# BlueBus.net
KiCad netlist of a schematic drawn in EAGLE
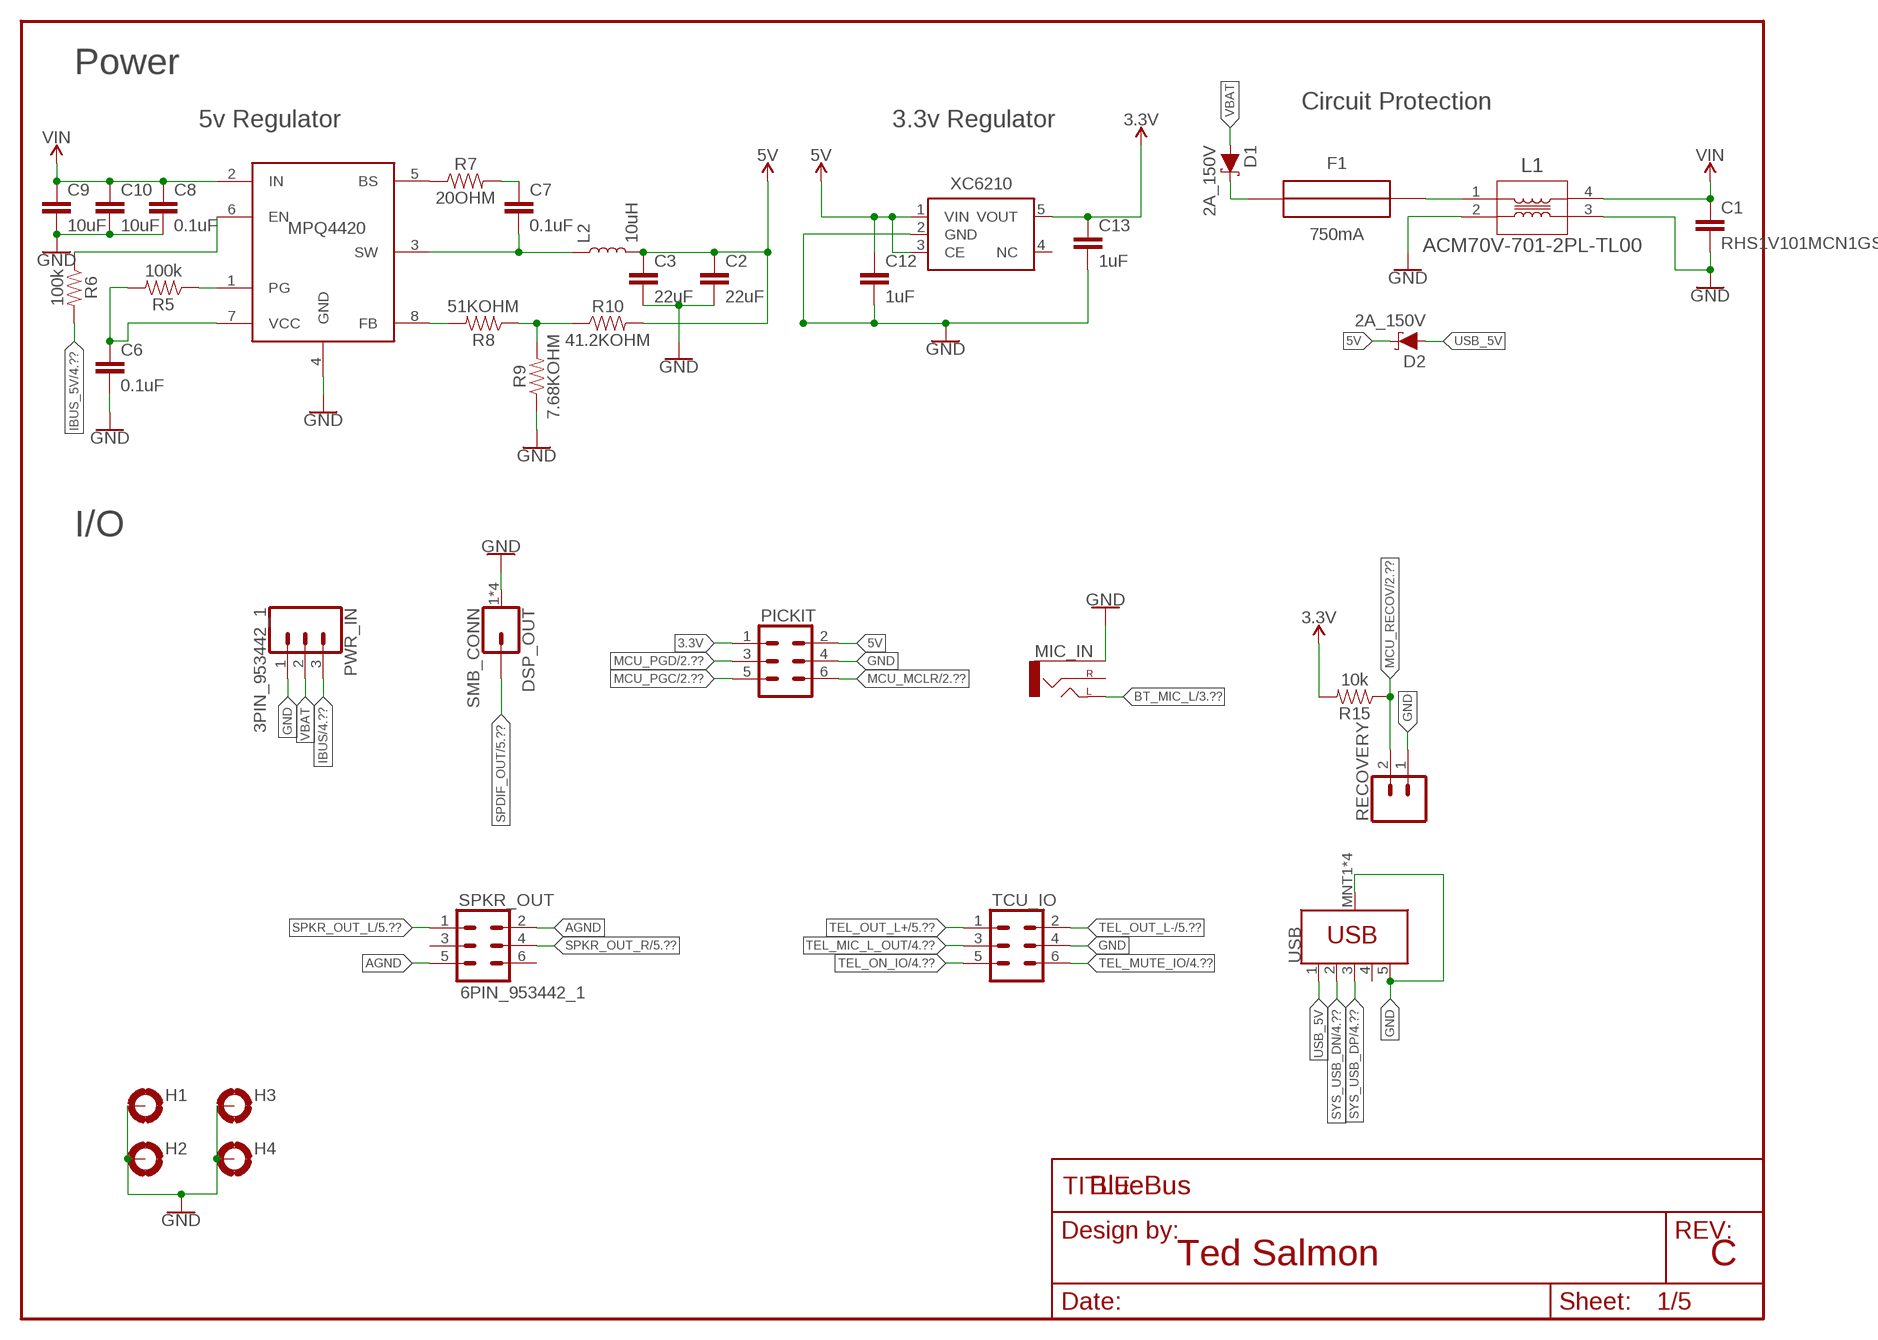
[diagram p0: schematic, sheet 1]
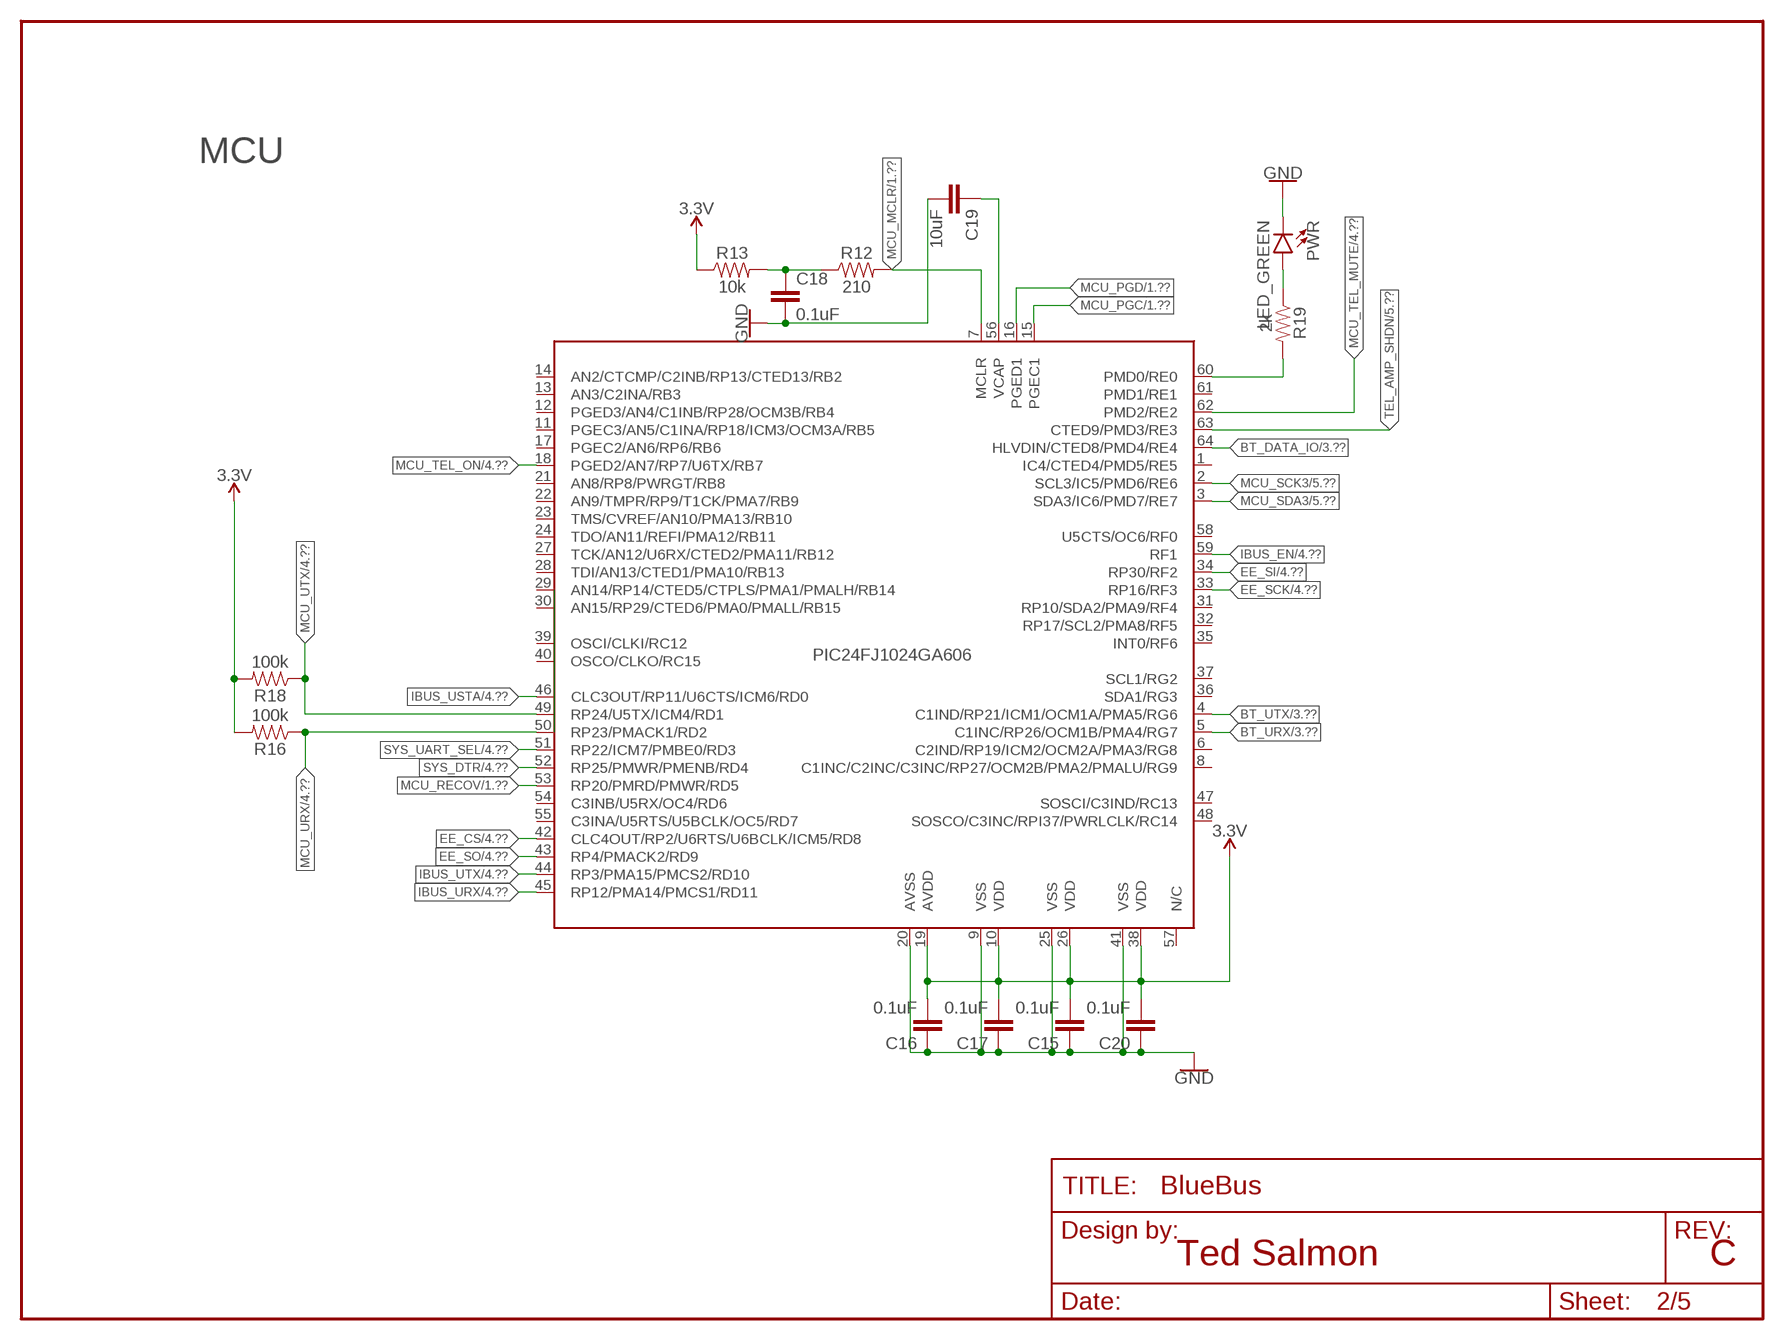
[diagram p1: schematic, sheet 2]
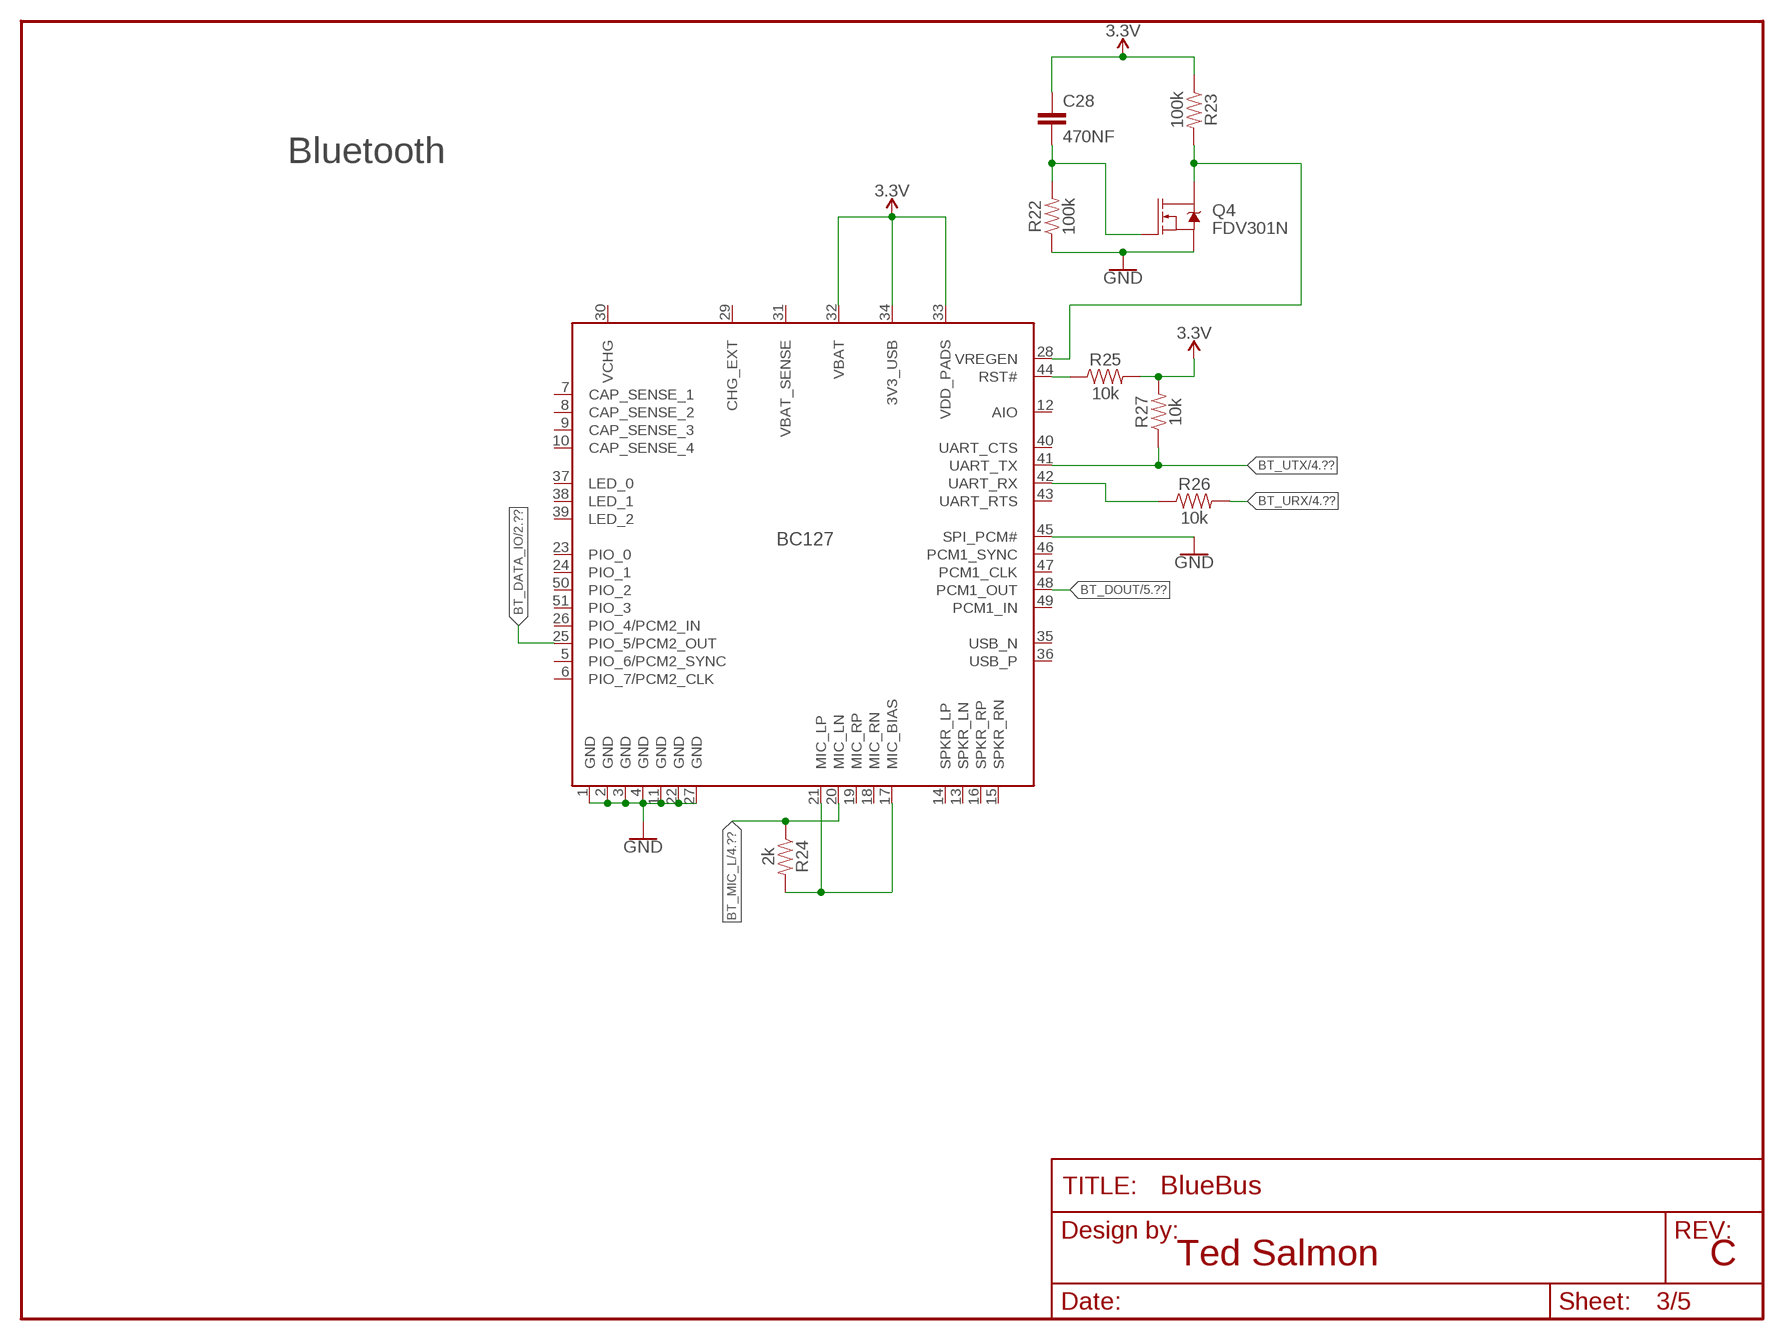
[diagram p2: schematic, sheet 3]
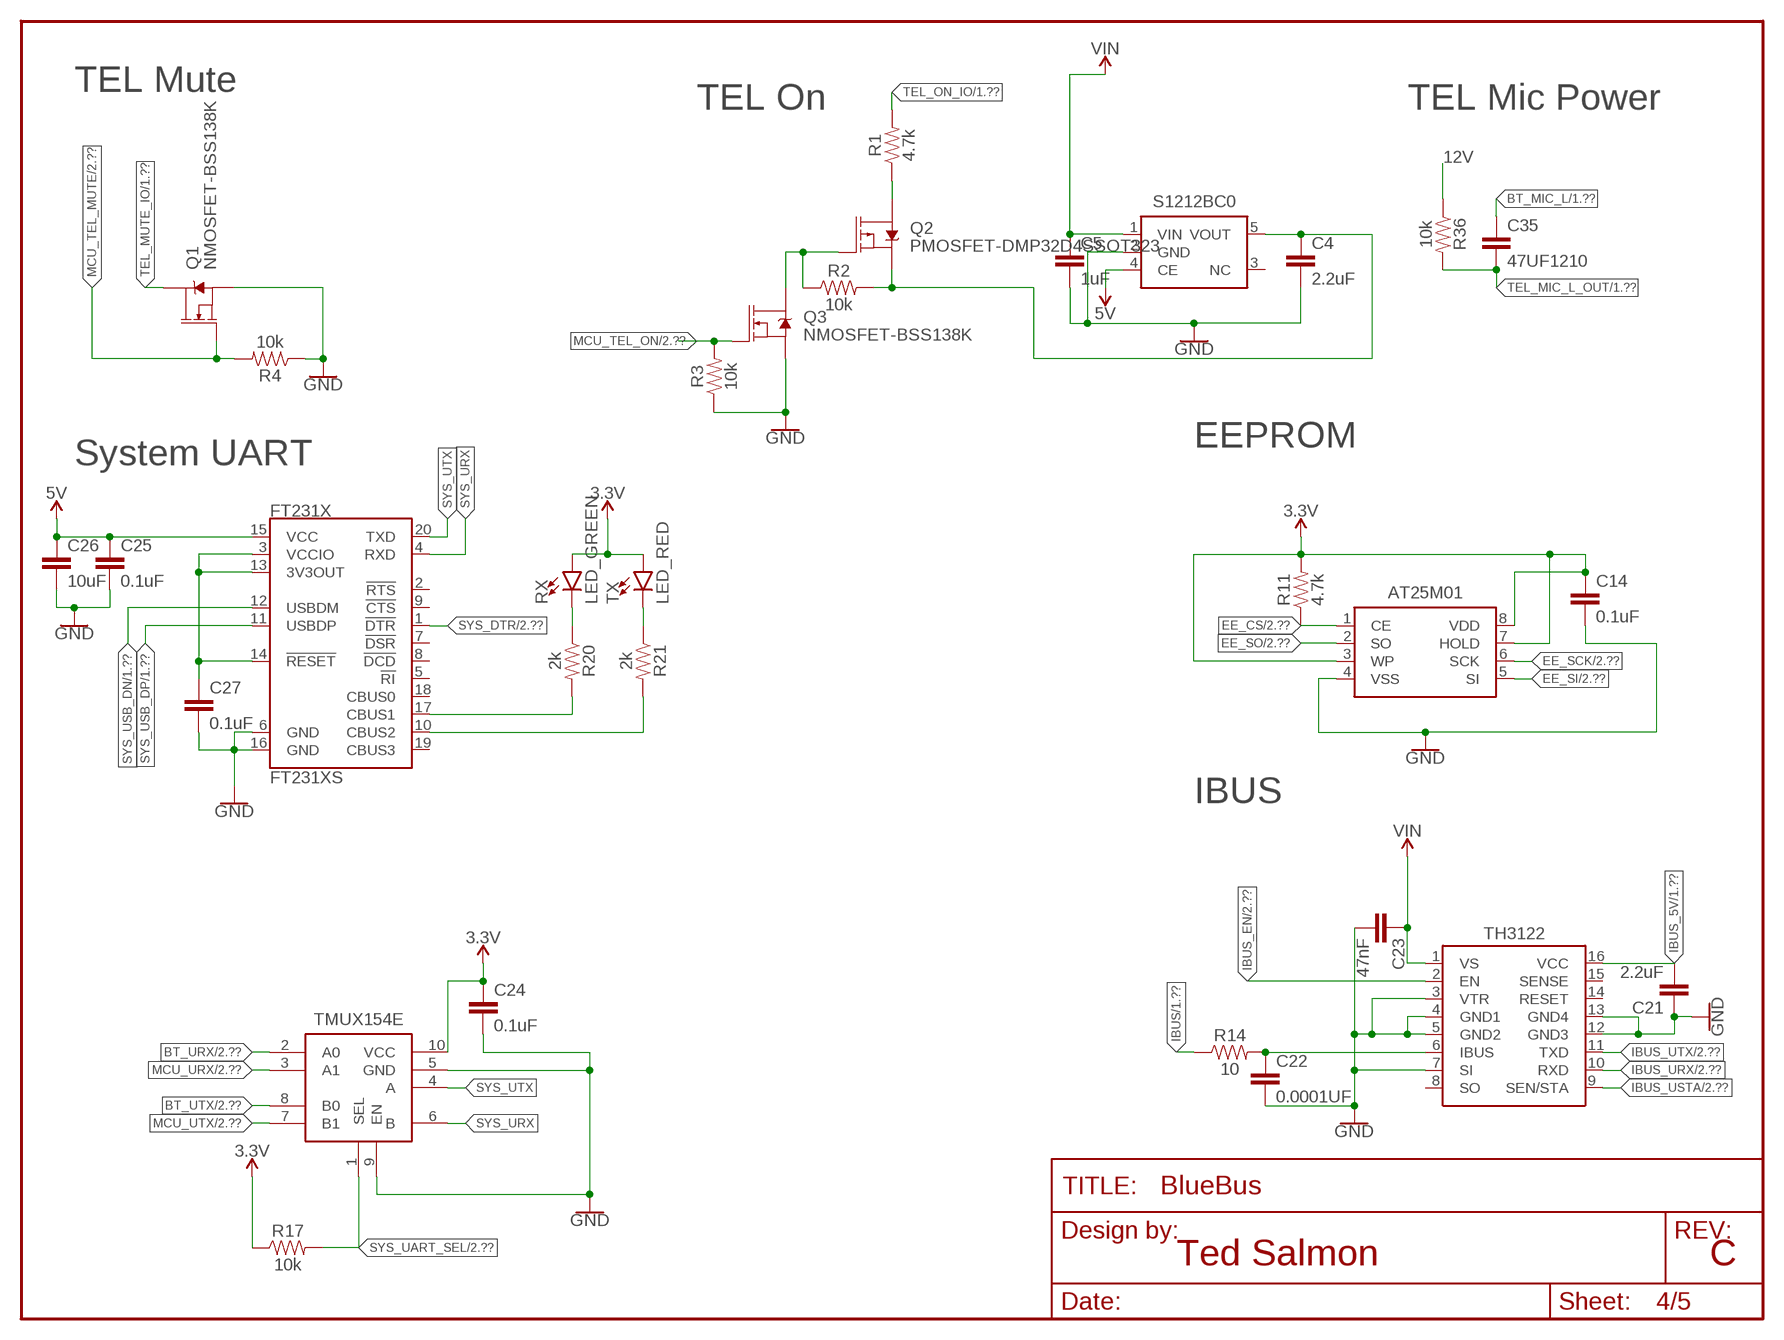
[diagram p3: schematic, sheet 4]
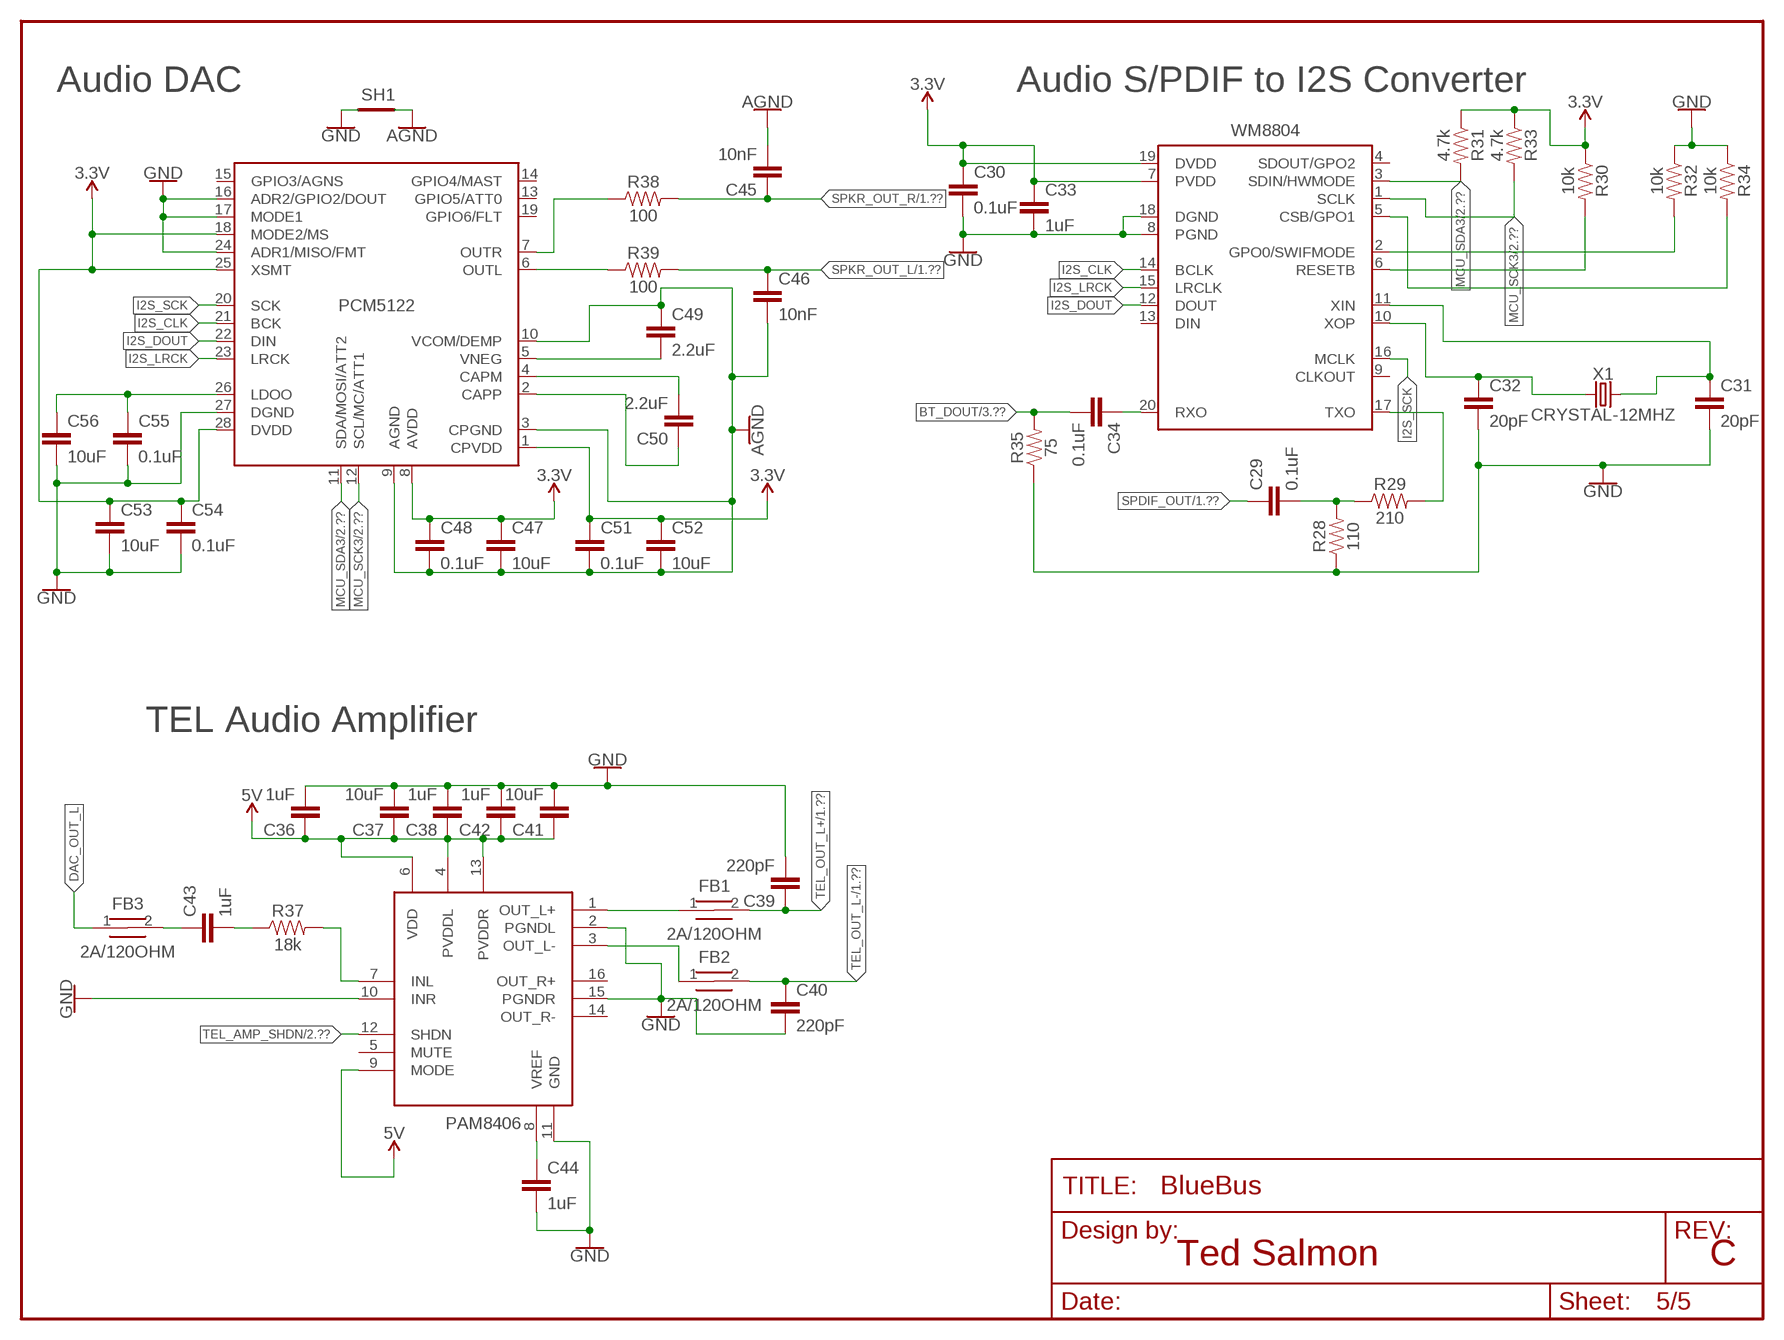
[diagram p4: schematic, sheet 5]

(export (version "E")
  (design (tool "Eeschema 10.0.6"))
  (components
    (comp (ref "C29")
      (value "0.1uF")
      (footprint "eagle-import:0805")
      (fields (field (name "MFG") "KEMET"))
      (libsource (lib "eagle-import") (part "0.1UF"))
    )
    (comp (ref "C30")
      (value "0.1uF")
      (footprint "eagle-import:0805")
      (fields (field (name "MFG") "KEMET"))
      (libsource (lib "eagle-import") (part "0.1UF"))
    )
    (comp (ref "C31")
      (value "20pF")
      (footprint "eagle-import:0805")
      (libsource (lib "eagle-import") (part "20PF"))
    )
    (comp (ref "C32")
      (value "20pF")
      (footprint "eagle-import:0805")
      (libsource (lib "eagle-import") (part "20PF"))
    )
    (comp (ref "C33")
      (value "1uF")
      (footprint "eagle-import:0805")
      (fields (field (name "MFG") "TDK"))
      (libsource (lib "eagle-import") (part "1UF"))
    )
    (comp (ref "C34")
      (value "0.1uF")
      (footprint "eagle-import:0805")
      (fields (field (name "MFG") "KEMET"))
      (libsource (lib "eagle-import") (part "0.1UF"))
    )
    (comp (ref "C36")
      (value "1uF")
      (footprint "eagle-import:0805")
      (fields (field (name "MFG") "TDK"))
      (libsource (lib "eagle-import") (part "1UF"))
    )
    (comp (ref "C37")
      (value "10uF")
      (footprint "eagle-import:0805")
      (fields (field (name "MFG") "TDK"))
      (libsource (lib "eagle-import") (part "10UF2012"))
    )
    (comp (ref "C38")
      (value "1uF")
      (footprint "eagle-import:0805")
      (fields (field (name "MFG") "TDK"))
      (libsource (lib "eagle-import") (part "1UF"))
    )
    (comp (ref "C39")
      (value "220pF")
      (footprint "eagle-import:0805")
      (fields (field (name "MFG") "KEMET"))
      (libsource (lib "eagle-import") (part "220PF"))
    )
    (comp (ref "C40")
      (value "220pF")
      (footprint "eagle-import:0805")
      (fields (field (name "MFG") "KEMET"))
      (libsource (lib "eagle-import") (part "220PF"))
    )
    (comp (ref "C41")
      (value "10uF")
      (footprint "eagle-import:0805")
      (fields (field (name "MFG") "TDK"))
      (libsource (lib "eagle-import") (part "10UF2012"))
    )
    (comp (ref "C42")
      (value "1uF")
      (footprint "eagle-import:0805")
      (fields (field (name "MFG") "TDK"))
      (libsource (lib "eagle-import") (part "1UF"))
    )
    (comp (ref "C43")
      (value "1uF")
      (footprint "eagle-import:0805")
      (fields (field (name "MFG") "TDK"))
      (libsource (lib "eagle-import") (part "1UF"))
    )
    (comp (ref "C44")
      (value "1uF")
      (footprint "eagle-import:0805")
      (fields (field (name "MFG") "TDK"))
      (libsource (lib "eagle-import") (part "1UF"))
    )
    (comp (ref "C45")
      (value "10nF")
      (footprint "eagle-import:0805")
      (fields (field (name "MFG") "KEMET"))
      (libsource (lib "eagle-import") (part "10NF"))
    )
    (comp (ref "C46")
      (value "10nF")
      (footprint "eagle-import:0805")
      (fields (field (name "MFG") "KEMET"))
      (libsource (lib "eagle-import") (part "10NF"))
    )
    (comp (ref "C47")
      (value "10uF")
      (footprint "eagle-import:0805")
      (fields (field (name "MFG") "TDK"))
      (libsource (lib "eagle-import") (part "10UF2012"))
    )
    (comp (ref "C48")
      (value "0.1uF")
      (footprint "eagle-import:0805")
      (fields (field (name "MFG") "KEMET"))
      (libsource (lib "eagle-import") (part "0.1UF"))
    )
    (comp (ref "C49")
      (value "2.2uF")
      (footprint "eagle-import:0805")
      (fields (field (name "MFG") "TDK"))
      (libsource (lib "eagle-import") (part "2.2UF"))
    )
    (comp (ref "C50")
      (value "2.2uF")
      (footprint "eagle-import:0805")
      (fields (field (name "MFG") "TDK"))
      (libsource (lib "eagle-import") (part "2.2UF"))
    )
    (comp (ref "C51")
      (value "0.1uF")
      (footprint "eagle-import:0805")
      (fields (field (name "MFG") "KEMET"))
      (libsource (lib "eagle-import") (part "0.1UF"))
    )
    (comp (ref "C52")
      (value "10uF")
      (footprint "eagle-import:0805")
      (fields (field (name "MFG") "TDK"))
      (libsource (lib "eagle-import") (part "10UF2012"))
    )
    (comp (ref "C53")
      (value "10uF")
      (footprint "eagle-import:0805")
      (fields (field (name "MFG") "TDK"))
      (libsource (lib "eagle-import") (part "10UF2012"))
    )
    (comp (ref "C54")
      (value "0.1uF")
      (footprint "eagle-import:0805")
      (fields (field (name "MFG") "KEMET"))
      (libsource (lib "eagle-import") (part "0.1UF"))
    )
    (comp (ref "C55")
      (value "0.1uF")
      (footprint "eagle-import:0805")
      (fields (field (name "MFG") "KEMET"))
      (libsource (lib "eagle-import") (part "0.1UF"))
    )
    (comp (ref "C56")
      (value "10uF")
      (footprint "eagle-import:0805")
      (fields (field (name "MFG") "TDK"))
      (libsource (lib "eagle-import") (part "10UF2012"))
    )
    (comp (ref "FB1")
      (value "2A/120OHM")
      (footprint "eagle-import:0805")
      (fields (field (name "MFG") "BOURNS"))
      (libsource (lib "eagle-import") (part "FERRITE_2A/120OHM"))
    )
    (comp (ref "FB2")
      (value "2A/120OHM")
      (footprint "eagle-import:0805")
      (fields (field (name "MFG") "BOURNS"))
      (libsource (lib "eagle-import") (part "FERRITE_2A/120OHM"))
    )
    (comp (ref "FB3")
      (value "2A/120OHM")
      (footprint "eagle-import:0805")
      (fields (field (name "MFG") "BOURNS"))
      (libsource (lib "eagle-import") (part "FERRITE_2A/120OHM"))
    )
    (comp (ref "FRAME5")
      (value "FRAME-LETTER")
      (footprint "eagle-import:DUMMY")
      (libsource (lib "eagle-import") (part "FRAME-LETTER"))
    )
    (comp (ref "PAM8406")
      (value "PAM8406")
      (footprint "eagle-import:SOP-16")
      (libsource (lib "eagle-import") (part "PAM8406"))
    )
    (comp (ref "PCM5122")
      (value "PCM5122")
      (footprint "eagle-import:TSSOP28")
      (libsource (lib "eagle-import") (part "PCM5122"))
    )
    (comp (ref "R28")
      (value "110")
      (footprint "eagle-import:0805")
      (libsource (lib "eagle-import") (part "110OHM"))
    )
    (comp (ref "R29")
      (value "210")
      (footprint "eagle-import:0805")
      (libsource (lib "eagle-import") (part "210OHM"))
    )
    (comp (ref "R30")
      (value "10k")
      (footprint "eagle-import:0805")
      (fields (field (name "MFG") "Panasonic"))
      (libsource (lib "eagle-import") (part "10KOHM"))
    )
    (comp (ref "R31")
      (value "4.7k")
      (footprint "eagle-import:0805")
      (fields (field (name "MFG") "Panasonic"))
      (libsource (lib "eagle-import") (part "4.7KOHM"))
    )
    (comp (ref "R32")
      (value "10k")
      (footprint "eagle-import:0805")
      (fields (field (name "MFG") "Panasonic"))
      (libsource (lib "eagle-import") (part "10KOHM"))
    )
    (comp (ref "R33")
      (value "4.7k")
      (footprint "eagle-import:0805")
      (fields (field (name "MFG") "Panasonic"))
      (libsource (lib "eagle-import") (part "4.7KOHM"))
    )
    (comp (ref "R34")
      (value "10k")
      (footprint "eagle-import:0805")
      (fields (field (name "MFG") "Panasonic"))
      (libsource (lib "eagle-import") (part "10KOHM"))
    )
    (comp (ref "R35")
      (value "75")
      (footprint "eagle-import:0805")
      (fields (field (name "MFG") "Panasonic"))
      (libsource (lib "eagle-import") (part "75OHM"))
    )
    (comp (ref "R37")
      (value "18k")
      (footprint "eagle-import:0805")
      (fields (field (name "MFG") "Panasonic"))
      (libsource (lib "eagle-import") (part "18KOHM"))
    )
    (comp (ref "R38")
      (value "100")
      (footprint "eagle-import:0805")
      (fields (field (name "MFG") "PANASONIC"))
      (libsource (lib "eagle-import") (part "100OHM"))
    )
    (comp (ref "R39")
      (value "100")
      (footprint "eagle-import:0805")
      (fields (field (name "MFG") "PANASONIC"))
      (libsource (lib "eagle-import") (part "100OHM"))
    )
    (comp (ref "SH1")
      (value "SHORTT5")
      (footprint "eagle-import:SHORT_TOP-50")
      (libsource (lib "eagle-import") (part "SHORTT5"))
    )
    (comp (ref "WM8804")
      (value "WM8804")
      (footprint "eagle-import:SSOP20")
      (libsource (lib "eagle-import") (part "WM8804"))
    )
    (comp (ref "X1")
      (value "CRYSTAL-12MHZ")
      (footprint "eagle-import:HC49")
      (libsource (lib "eagle-import") (part "CRYSTAL-12MHZ"))
    )
    (comp (ref "BC127")
      (value "BC127")
      (footprint "eagle-import:BC127")
      (libsource (lib "eagle-import") (part "BC127"))
    )
    (comp (ref "C28")
      (value "470NF")
      (footprint "eagle-import:0805")
      (fields (field (name "MFG") "TDK"))
      (libsource (lib "eagle-import") (part "470NF"))
    )
    (comp (ref "FRAME4")
      (value "FRAME-LETTER")
      (footprint "eagle-import:DUMMY")
      (libsource (lib "eagle-import") (part "FRAME-LETTER"))
    )
    (comp (ref "Q4")
      (value "FDV301N")
      (footprint "eagle-import:SOT-23")
      (libsource (lib "eagle-import") (part "FDV301N"))
    )
    (comp (ref "R22")
      (value "100k")
      (footprint "eagle-import:0805")
      (libsource (lib "eagle-import") (part "100KOHM"))
    )
    (comp (ref "R23")
      (value "100k")
      (footprint "eagle-import:0805")
      (libsource (lib "eagle-import") (part "100KOHM"))
    )
    (comp (ref "R24")
      (value "2k")
      (footprint "eagle-import:0805")
      (fields (field (name "MFG") "ROHM"))
      (libsource (lib "eagle-import") (part "2KOHM"))
    )
    (comp (ref "R25")
      (value "10k")
      (footprint "eagle-import:0805")
      (fields (field (name "MFG") "Panasonic"))
      (libsource (lib "eagle-import") (part "10KOHM"))
    )
    (comp (ref "R26")
      (value "10k")
      (footprint "eagle-import:0805")
      (fields (field (name "MFG") "Panasonic"))
      (libsource (lib "eagle-import") (part "10KOHM"))
    )
    (comp (ref "R27")
      (value "10k")
      (footprint "eagle-import:0805")
      (fields (field (name "MFG") "Panasonic"))
      (libsource (lib "eagle-import") (part "10KOHM"))
    )
    (comp (ref "C15")
      (value "0.1uF")
      (footprint "eagle-import:0805")
      (fields (field (name "MFG") "KEMET"))
      (libsource (lib "eagle-import") (part "0.1UF"))
    )
    (comp (ref "C16")
      (value "0.1uF")
      (footprint "eagle-import:0805")
      (fields (field (name "MFG") "KEMET"))
      (libsource (lib "eagle-import") (part "0.1UF"))
    )
    (comp (ref "C17")
      (value "0.1uF")
      (footprint "eagle-import:0805")
      (fields (field (name "MFG") "KEMET"))
      (libsource (lib "eagle-import") (part "0.1UF"))
    )
    (comp (ref "C18")
      (value "0.1uF")
      (footprint "eagle-import:0805")
      (fields (field (name "MFG") "KEMET"))
      (libsource (lib "eagle-import") (part "0.1UF"))
    )
    (comp (ref "C19")
      (value "10uF")
      (footprint "eagle-import:0805")
      (fields (field (name "MFG") "TDK"))
      (libsource (lib "eagle-import") (part "10UF2012"))
    )
    (comp (ref "C20")
      (value "0.1uF")
      (footprint "eagle-import:0805")
      (fields (field (name "MFG") "KEMET"))
      (libsource (lib "eagle-import") (part "0.1UF"))
    )
    (comp (ref "FRAME2")
      (value "FRAME-LETTER")
      (footprint "eagle-import:DUMMY")
      (libsource (lib "eagle-import") (part "FRAME-LETTER"))
    )
    (comp (ref "PIC24FJ1024GA606")
      (value "PIC24FJ1024GA606")
      (footprint "eagle-import:TQFP64")
      (libsource (lib "eagle-import") (part "PIC24FJ1024GA606"))
    )
    (comp (ref "PWR")
      (value "LED_GREEN")
      (footprint "eagle-import:LED-0805")
      (libsource (lib "eagle-import") (part "LED_GREEN"))
    )
    (comp (ref "R12")
      (value "210")
      (footprint "eagle-import:0805")
      (libsource (lib "eagle-import") (part "210OHM"))
    )
    (comp (ref "R13")
      (value "10k")
      (footprint "eagle-import:0805")
      (fields (field (name "MFG") "Panasonic"))
      (libsource (lib "eagle-import") (part "10KOHM"))
    )
    (comp (ref "R16")
      (value "100k")
      (footprint "eagle-import:0805")
      (libsource (lib "eagle-import") (part "100KOHM"))
    )
    (comp (ref "R18")
      (value "100k")
      (footprint "eagle-import:0805")
      (libsource (lib "eagle-import") (part "100KOHM"))
    )
    (comp (ref "R19")
      (value "2k")
      (footprint "eagle-import:0805")
      (fields (field (name "MFG") "ROHM"))
      (libsource (lib "eagle-import") (part "2KOHM"))
    )
    (comp (ref "AT25M01")
      (value "AT25M01-SHM")
      (footprint "eagle-import:SOIJ-8")
      (libsource (lib "eagle-import") (part "AT25M01-SHM"))
    )
    (comp (ref "C4")
      (value "2.2uF")
      (footprint "eagle-import:0805")
      (fields (field (name "MFG") "TDK"))
      (libsource (lib "eagle-import") (part "2.2UF"))
    )
    (comp (ref "C5")
      (value "1uF")
      (footprint "eagle-import:0805")
      (fields (field (name "MFG") "TDK"))
      (libsource (lib "eagle-import") (part "1UF"))
    )
    (comp (ref "C14")
      (value "0.1uF")
      (footprint "eagle-import:0805")
      (fields (field (name "MFG") "KEMET"))
      (libsource (lib "eagle-import") (part "0.1UF"))
    )
    (comp (ref "C21")
      (value "2.2uF")
      (footprint "eagle-import:0805")
      (fields (field (name "MFG") "TDK"))
      (libsource (lib "eagle-import") (part "2.2UF"))
    )
    (comp (ref "C22")
      (value "0.0001UF")
      (footprint "eagle-import:0805")
      (libsource (lib "eagle-import") (part "0.0001UF"))
    )
    (comp (ref "C23")
      (value "47nF")
      (footprint "eagle-import:0805")
      (fields (field (name "MFG") "AVX"))
      (libsource (lib "eagle-import") (part "47NF"))
    )
    (comp (ref "C24")
      (value "0.1uF")
      (footprint "eagle-import:0805")
      (fields (field (name "MFG") "KEMET"))
      (libsource (lib "eagle-import") (part "0.1UF"))
    )
    (comp (ref "C25")
      (value "0.1uF")
      (footprint "eagle-import:0805")
      (fields (field (name "MFG") "KEMET"))
      (libsource (lib "eagle-import") (part "0.1UF"))
    )
    (comp (ref "C26")
      (value "10uF")
      (footprint "eagle-import:0805")
      (fields (field (name "MFG") "TDK"))
      (libsource (lib "eagle-import") (part "10UF2012"))
    )
    (comp (ref "C27")
      (value "0.1uF")
      (footprint "eagle-import:0805")
      (fields (field (name "MFG") "KEMET"))
      (libsource (lib "eagle-import") (part "0.1UF"))
    )
    (comp (ref "C35")
      (value "47UF1210")
      (footprint "eagle-import:1210")
      (libsource (lib "eagle-import") (part "47UF1210"))
    )
    (comp (ref "FRAME3")
      (value "FRAME-LETTER")
      (footprint "eagle-import:DUMMY")
      (libsource (lib "eagle-import") (part "FRAME-LETTER"))
    )
    (comp (ref "FT231X")
      (value "FT231XS")
      (footprint "eagle-import:SSOP20_L")
      (libsource (lib "eagle-import") (part "FT231XS"))
    )
    (comp (ref "Q1")
      (value "NMOSFET-BSS138K")
      (footprint "eagle-import:SOT-23")
      (libsource (lib "eagle-import") (part "NMOSFET-BSS138K"))
    )
    (comp (ref "Q2")
      (value "PMOSFET-DMP32D4SSOT323")
      (footprint "eagle-import:SOT323")
      (libsource (lib "eagle-import") (part "PMOSFET-DMP32D4SSOT323"))
    )
    (comp (ref "Q3")
      (value "NMOSFET-BSS138K")
      (footprint "eagle-import:SOT-23")
      (libsource (lib "eagle-import") (part "NMOSFET-BSS138K"))
    )
    (comp (ref "R1")
      (value "4.7k")
      (footprint "eagle-import:0805")
      (fields (field (name "MFG") "Panasonic"))
      (libsource (lib "eagle-import") (part "4.7KOHM"))
    )
    (comp (ref "R2")
      (value "10k")
      (footprint "eagle-import:0805")
      (fields (field (name "MFG") "Panasonic"))
      (libsource (lib "eagle-import") (part "10KOHM"))
    )
    (comp (ref "R3")
      (value "10k")
      (footprint "eagle-import:0805")
      (fields (field (name "MFG") "Panasonic"))
      (libsource (lib "eagle-import") (part "10KOHM"))
    )
    (comp (ref "R4")
      (value "10k")
      (footprint "eagle-import:0805")
      (fields (field (name "MFG") "Panasonic"))
      (libsource (lib "eagle-import") (part "10KOHM"))
    )
    (comp (ref "R11")
      (value "4.7k")
      (footprint "eagle-import:0805")
      (fields (field (name "MFG") "Panasonic"))
      (libsource (lib "eagle-import") (part "4.7KOHM"))
    )
    (comp (ref "R14")
      (value "10")
      (footprint "eagle-import:0805")
      (fields (field (name "MFG") "Panasonic"))
      (libsource (lib "eagle-import") (part "10OHM"))
    )
    (comp (ref "R17")
      (value "10k")
      (footprint "eagle-import:0805")
      (fields (field (name "MFG") "Panasonic"))
      (libsource (lib "eagle-import") (part "10KOHM"))
    )
    (comp (ref "R20")
      (value "2k")
      (footprint "eagle-import:0805")
      (fields (field (name "MFG") "ROHM"))
      (libsource (lib "eagle-import") (part "2KOHM"))
    )
    (comp (ref "R21")
      (value "2k")
      (footprint "eagle-import:0805")
      (fields (field (name "MFG") "ROHM"))
      (libsource (lib "eagle-import") (part "2KOHM"))
    )
    (comp (ref "R36")
      (value "10k")
      (footprint "eagle-import:0805")
      (fields (field (name "MFG") "Panasonic"))
      (libsource (lib "eagle-import") (part "10KOHM"))
    )
    (comp (ref "RX")
      (value "LED_GREEN")
      (footprint "eagle-import:LED-0805")
      (libsource (lib "eagle-import") (part "LED_GREEN"))
    )
    (comp (ref "S1212BC0")
      (value "S-1212BC0-M5T1U")
      (footprint "eagle-import:SOT23-5")
      (libsource (lib "eagle-import") (part "S-1212BC0-M5T1U"))
    )
    (comp (ref "TH3122")
      (value "TH3122.4")
      (footprint "eagle-import:SOIC16DF")
      (libsource (lib "eagle-import") (part "TH3122.4"))
    )
    (comp (ref "TMUX154E")
      (value "TMUX154E")
      (footprint "eagle-import:VSSOP10")
      (libsource (lib "eagle-import") (part "TMUX154E"))
    )
    (comp (ref "TX")
      (value "LED_RED")
      (footprint "eagle-import:LED-0805")
      (libsource (lib "eagle-import") (part "LED_RED"))
    )
    (comp (ref "C1")
      (value "RHS1V101MCN1GS")
      (footprint "eagle-import:RHS1V101MCN1GS")
      (fields (field (name "MFG") "Nichicon"))
      (libsource (lib "eagle-import") (part "RHS1V101MCN1GS"))
    )
    (comp (ref "C2")
      (value "22uF")
      (footprint "eagle-import:0805")
      (fields (field (name "MFG") "TDK"))
      (libsource (lib "eagle-import") (part "22UF"))
    )
    (comp (ref "C3")
      (value "22uF")
      (footprint "eagle-import:0805")
      (fields (field (name "MFG") "TDK"))
      (libsource (lib "eagle-import") (part "22UF"))
    )
    (comp (ref "C6")
      (value "0.1uF")
      (footprint "eagle-import:0805")
      (fields (field (name "MFG") "KEMET"))
      (libsource (lib "eagle-import") (part "0.1UF"))
    )
    (comp (ref "C7")
      (value "0.1uF")
      (footprint "eagle-import:0805")
      (fields (field (name "MFG") "KEMET"))
      (libsource (lib "eagle-import") (part "0.1UF"))
    )
    (comp (ref "C8")
      (value "0.1uF")
      (footprint "eagle-import:0805")
      (fields (field (name "MFG") "KEMET"))
      (libsource (lib "eagle-import") (part "0.1UF"))
    )
    (comp (ref "C9")
      (value "10uF")
      (footprint "eagle-import:1206")
      (fields (field (name "MFG") "TDK"))
      (libsource (lib "eagle-import") (part "10UF"))
    )
    (comp (ref "C10")
      (value "10uF")
      (footprint "eagle-import:1206")
      (fields (field (name "MFG") "TDK"))
      (libsource (lib "eagle-import") (part "10UF"))
    )
    (comp (ref "C12")
      (value "1uF")
      (footprint "eagle-import:0805")
      (fields (field (name "MFG") "TDK"))
      (libsource (lib "eagle-import") (part "1UF"))
    )
    (comp (ref "C13")
      (value "1uF")
      (footprint "eagle-import:0805")
      (fields (field (name "MFG") "TDK"))
      (libsource (lib "eagle-import") (part "1UF"))
    )
    (comp (ref "D1")
      (value "2A_150V")
      (footprint "eagle-import:SOD123FL-2")
      (fields (field (name "MFG") "MCC"))
      (libsource (lib "eagle-import") (part "SMD2150PL_2A_150V"))
    )
    (comp (ref "D2")
      (value "2A_150V")
      (footprint "eagle-import:SOD123FL-2")
      (fields (field (name "MFG") "MCC"))
      (libsource (lib "eagle-import") (part "SMD2150PL_2A_150V"))
    )
    (comp (ref "DSP_OUT")
      (value "SMB_CONN")
      (footprint "eagle-import:MOLEX_SMB")
      (libsource (lib "eagle-import") (part "SMB_CONN"))
    )
    (comp (ref "F1")
      (value "750mA")
      (footprint "eagle-import:LITTLEFUSE")
      (fields (field (name "MFG") "LITTLEBLOCK"))
      (libsource (lib "eagle-import") (part "LITTLEBLOCK_FUSE_.75A"))
    )
    (comp (ref "FRAME1")
      (value "FRAME-LETTER")
      (footprint "eagle-import:DUMMY")
      (libsource (lib "eagle-import") (part "FRAME-LETTER"))
    )
    (comp (ref "H1")
      (value "2,2-PAD")
      (footprint "eagle-import:2.2-PAD")
      (libsource (lib "eagle-import") (part "2,2-PAD"))
    )
    (comp (ref "H2")
      (value "2,2-PAD")
      (footprint "eagle-import:2.2-PAD")
      (libsource (lib "eagle-import") (part "2,2-PAD"))
    )
    (comp (ref "H3")
      (value "2,2-PAD")
      (footprint "eagle-import:2.2-PAD")
      (libsource (lib "eagle-import") (part "2,2-PAD"))
    )
    (comp (ref "H4")
      (value "2,2-PAD")
      (footprint "eagle-import:2.2-PAD")
      (libsource (lib "eagle-import") (part "2,2-PAD"))
    )
    (comp (ref "L1")
      (value "ACM70V-701-2PL-TL00")
      (footprint "eagle-import:ACM70V-701-2PL-TL00")
      (fields (field (name "MFG") "TDK"))
      (libsource (lib "eagle-import") (part "ACM70V-701-2PL-TL00"))
    )
    (comp (ref "L2")
      (value "10uH")
      (footprint "eagle-import:MPL-SE5040")
      (fields (field (name "MFG") "MPS"))
      (libsource (lib "eagle-import") (part "MPL-SE5040-100"))
    )
    (comp (ref "MIC_IN")
      (value "AUDIO-CUI-SJ-3523-SMT")
      (footprint "eagle-import:AUDIO-CUI-SJ-352X-SMT")
      (libsource (lib "eagle-import") (part "AUDIO-CUI-SJ-3523-SMT"))
    )
    (comp (ref "MPQ4420")
      (value "MPQ4420")
      (footprint "eagle-import:TSOT23-8")
      (libsource (lib "eagle-import") (part "MPQ4420"))
    )
    (comp (ref "PICKIT")
      (value "6PIN_JUMPER")
      (footprint "eagle-import:2X3")
      (libsource (lib "eagle-import") (part "6PIN_JUMPER"))
    )
    (comp (ref "PWR_IN")
      (value "3PIN_953442_1")
      (footprint "eagle-import:TE_MQS_3PIN")
      (libsource (lib "eagle-import") (part "3PIN_953442_1"))
    )
    (comp (ref "R5")
      (value "100k")
      (footprint "eagle-import:0805")
      (libsource (lib "eagle-import") (part "100KOHM"))
    )
    (comp (ref "R6")
      (value "100k")
      (footprint "eagle-import:0805")
      (libsource (lib "eagle-import") (part "100KOHM"))
    )
    (comp (ref "R7")
      (value "20OHM")
      (footprint "eagle-import:0805")
      (libsource (lib "eagle-import") (part "20OHM"))
    )
    (comp (ref "R8")
      (value "51KOHM")
      (footprint "eagle-import:0805")
      (libsource (lib "eagle-import") (part "51KOHM"))
    )
    (comp (ref "R9")
      (value "7.68KOHM")
      (footprint "eagle-import:0805")
      (libsource (lib "eagle-import") (part "7.68KOHM"))
    )
    (comp (ref "R10")
      (value "41.2KOHM")
      (footprint "eagle-import:0805")
      (libsource (lib "eagle-import") (part "41.2KOHM"))
    )
    (comp (ref "R15")
      (value "10k")
      (footprint "eagle-import:0805")
      (fields (field (name "MFG") "Panasonic"))
      (libsource (lib "eagle-import") (part "10KOHM"))
    )
    (comp (ref "RECOVERY")
      (value "2PIN_JUMPER")
      (footprint "eagle-import:1X02")
      (libsource (lib "eagle-import") (part "2PIN_JUMPER"))
    )
    (comp (ref "SPKR_OUT")
      (value "6PIN_953442_1")
      (footprint "eagle-import:TE_MQS_6PIN")
      (libsource (lib "eagle-import") (part "6PIN_953442_1"))
    )
    (comp (ref "TCU_IO")
      (value "6PIN_5_103166_1")
      (footprint "eagle-import:TE_AMPMODU_6_PIN")
      (libsource (lib "eagle-import") (part "6PIN_5_103166_1"))
    )
    (comp (ref "USB")
      (value "USB3080-30-01-A")
      (footprint "eagle-import:USB3080-30-01-A")
      (fields (field (name "MFG") "GCT"))
      (libsource (lib "eagle-import") (part "USB3080-30-01-A"))
    )
    (comp (ref "XC6210")
      (value "XC6210SOT25")
      (footprint "eagle-import:SOT23-5")
      (libsource (lib "eagle-import") (part "XC6210SOT25"))
    )
  )
  (nets
    (net (code "1") (name "3.3V") (class "Default")
      (node (ref "AT25M01") (pin "3") (pinfunction "WP_3") (pintype "bidirectional"))
      (node (ref "AT25M01") (pin "7") (pinfunction "HOLD_7") (pintype "bidirectional"))
      (node (ref "AT25M01") (pin "8") (pinfunction "VDD_8") (pintype "power_in"))
      (node (ref "BC127") (pin "32") (pinfunction "VBAT_32") (pintype "bidirectional"))
      (node (ref "BC127") (pin "33") (pinfunction "VDD_PADS_33") (pintype "power_in"))
      (node (ref "BC127") (pin "34") (pinfunction "3V3_USB_34") (pintype "power_in"))
      (node (ref "C13") (pin "1") (pinfunction "1_1") (pintype "passive"))
      (node (ref "C14") (pin "1") (pinfunction "1_1") (pintype "passive"))
      (node (ref "C15") (pin "2") (pinfunction "2_2") (pintype "passive"))
      (node (ref "C16") (pin "2") (pinfunction "2_2") (pintype "passive"))
      (node (ref "C17") (pin "2") (pinfunction "2_2") (pintype "passive"))
      (node (ref "C20") (pin "2") (pinfunction "2_2") (pintype "passive"))
      (node (ref "C24") (pin "1") (pinfunction "1_1") (pintype "passive"))
      (node (ref "C28") (pin "1") (pinfunction "1_1") (pintype "passive"))
      (node (ref "C30") (pin "1") (pinfunction "1_1") (pintype "passive"))
      (node (ref "C33") (pin "1") (pinfunction "1_1") (pintype "passive"))
      (node (ref "C47") (pin "1") (pinfunction "1_1") (pintype "passive"))
      (node (ref "C48") (pin "1") (pinfunction "1_1") (pintype "passive"))
      (node (ref "C51") (pin "1") (pinfunction "1_1") (pintype "passive"))
      (node (ref "C52") (pin "1") (pinfunction "1_1") (pintype "passive"))
      (node (ref "C53") (pin "1") (pinfunction "1_1") (pintype "passive"))
      (node (ref "C54") (pin "1") (pinfunction "1_1") (pintype "passive"))
      (node (ref "PCM5122") (pin "1") (pinfunction "CPVDD_1") (pintype "power_in"))
      (node (ref "PCM5122") (pin "18") (pinfunction "MODE2/MS_18") (pintype "bidirectional"))
      (node (ref "PCM5122") (pin "25") (pinfunction "XSMT_25") (pintype "input"))
      (node (ref "PCM5122") (pin "28") (pinfunction "DVDD_28") (pintype "power_in"))
      (node (ref "PCM5122") (pin "8") (pinfunction "AVDD_8") (pintype "power_in"))
      (node (ref "PIC24FJ1024GA606") (pin "10") (pinfunction "VDD_10") (pintype "power_in"))
      (node (ref "PIC24FJ1024GA606") (pin "19") (pinfunction "AVDD_19") (pintype "power_in"))
      (node (ref "PIC24FJ1024GA606") (pin "26") (pinfunction "VDD_26") (pintype "power_in"))
      (node (ref "PIC24FJ1024GA606") (pin "38") (pinfunction "VDD_38") (pintype "power_in"))
      (node (ref "PICKIT") (pin "1") (pinfunction "1_1") (pintype "bidirectional"))
      (node (ref "R11") (pin "2") (pinfunction "2_2") (pintype "passive"))
      (node (ref "R13") (pin "1") (pinfunction "1_1") (pintype "passive"))
      (node (ref "R15") (pin "2") (pinfunction "2_2") (pintype "passive"))
      (node (ref "R16") (pin "2") (pinfunction "2_2") (pintype "passive"))
      (node (ref "R17") (pin "1") (pinfunction "1_1") (pintype "passive"))
      (node (ref "R18") (pin "2") (pinfunction "2_2") (pintype "passive"))
      (node (ref "R23") (pin "1") (pinfunction "1_1") (pintype "passive"))
      (node (ref "R25") (pin "2") (pinfunction "2_2") (pintype "passive"))
      (node (ref "R27") (pin "2") (pinfunction "2_2") (pintype "passive"))
      (node (ref "R30") (pin "1") (pinfunction "1_1") (pintype "passive"))
      (node (ref "R31") (pin "1") (pinfunction "1_1") (pintype "passive"))
      (node (ref "R33") (pin "1") (pinfunction "1_1") (pintype "passive"))
      (node (ref "RX") (pin "+") (pinfunction "A_+") (pintype "passive"))
      (node (ref "TMUX154E") (pin "10") (pinfunction "VCC_10") (pintype "power_in"))
      (node (ref "TX") (pin "+") (pinfunction "A_+") (pintype "passive"))
      (node (ref "WM8804") (pin "19") (pinfunction "DVDD_19") (pintype "power_in"))
      (node (ref "WM8804") (pin "7") (pinfunction "PVDD_7") (pintype "power_in"))
      (node (ref "XC6210") (pin "5") (pinfunction "VOUT_5") (pintype "power_in"))
    )
    (net (code "2") (name "5V") (class "Default")
      (node (ref "C12") (pin "1") (pinfunction "1_1") (pintype "passive"))
      (node (ref "C2") (pin "1") (pinfunction "1_1") (pintype "passive"))
      (node (ref "C25") (pin "1") (pinfunction "1_1") (pintype "passive"))
      (node (ref "C26") (pin "1") (pinfunction "1_1") (pintype "passive"))
      (node (ref "C3") (pin "1") (pinfunction "1_1") (pintype "passive"))
      (node (ref "C36") (pin "1") (pinfunction "1_1") (pintype "passive"))
      (node (ref "C37") (pin "1") (pinfunction "1_1") (pintype "passive"))
      (node (ref "C38") (pin "1") (pinfunction "1_1") (pintype "passive"))
      (node (ref "C41") (pin "1") (pinfunction "1_1") (pintype "passive"))
      (node (ref "C42") (pin "1") (pinfunction "1_1") (pintype "passive"))
      (node (ref "D2") (pin "C") (pinfunction "C_C") (pintype "passive"))
      (node (ref "FT231X") (pin "15") (pinfunction "VCC_15") (pintype "bidirectional"))
      (node (ref "L2") (pin "2") (pinfunction "2_2") (pintype "passive"))
      (node (ref "PAM8406") (pin "13") (pinfunction "PVDDR_13") (pintype "bidirectional"))
      (node (ref "PAM8406") (pin "4") (pinfunction "PVDDL_4") (pintype "bidirectional"))
      (node (ref "PAM8406") (pin "6") (pinfunction "VDD_6") (pintype "bidirectional"))
      (node (ref "PAM8406") (pin "9") (pinfunction "MODE_9") (pintype "input"))
      (node (ref "PICKIT") (pin "2") (pinfunction "2_2") (pintype "bidirectional"))
      (node (ref "R10") (pin "2") (pinfunction "2_2") (pintype "passive"))
      (node (ref "S1212BC0") (pin "4") (pinfunction "CE_4") (pintype "power_in"))
      (node (ref "XC6210") (pin "1") (pinfunction "VIN_1") (pintype "power_in"))
      (node (ref "XC6210") (pin "3") (pinfunction "CE_3") (pintype "power_in"))
    )
    (net (code "3") (name "12V") (class "Default")
      (node (ref "C4") (pin "1") (pinfunction "1_1") (pintype "passive"))
      (node (ref "Q2") (pin "2") (pinfunction "S_2") (pintype "bidirectional"))
      (node (ref "R2") (pin "2") (pinfunction "2_2") (pintype "passive"))
      (node (ref "R36") (pin "1") (pinfunction "1_1") (pintype "passive"))
      (node (ref "S1212BC0") (pin "5") (pinfunction "VOUT_5") (pintype "power_in"))
    )
    (net (code "4") (name "AGND") (class "Default")
      (node (ref "C45") (pin "2") (pinfunction "2_2") (pintype "passive"))
      (node (ref "C46") (pin "2") (pinfunction "2_2") (pintype "passive"))
      (node (ref "C47") (pin "2") (pinfunction "2_2") (pintype "passive"))
      (node (ref "C48") (pin "2") (pinfunction "2_2") (pintype "passive"))
      (node (ref "C49") (pin "1") (pinfunction "1_1") (pintype "passive"))
      (node (ref "C51") (pin "2") (pinfunction "2_2") (pintype "passive"))
      (node (ref "C52") (pin "2") (pinfunction "2_2") (pintype "passive"))
      (node (ref "PCM5122") (pin "10") (pinfunction "VCOM/DEMP_10") (pintype "input"))
      (node (ref "PCM5122") (pin "3") (pinfunction "CPGND_3") (pintype "bidirectional"))
      (node (ref "PCM5122") (pin "9") (pinfunction "AGND_9") (pintype "bidirectional"))
      (node (ref "SH1") (pin "2") (pinfunction "P$2_2") (pintype "bidirectional"))
      (node (ref "SPKR_OUT") (pin "2") (pinfunction "2_2") (pintype "bidirectional"))
      (node (ref "SPKR_OUT") (pin "5") (pinfunction "5_5") (pintype "bidirectional"))
    )
    (net (code "5") (name "BT_DATA_IO") (class "Default")
      (node (ref "BC127") (pin "25") (pinfunction "PIO_5/PCM2_OUT_25") (pintype "bidirectional"))
      (node (ref "PIC24FJ1024GA606") (pin "64") (pinfunction "HLVDIN/CTED8/PMD4/RE4_64") (pintype "bidirectional"))
    )
    (net (code "6") (name "BT_DOUT") (class "Default")
      (node (ref "BC127") (pin "48") (pinfunction "PCM1_OUT_48") (pintype "bidirectional"))
      (node (ref "C34") (pin "2") (pinfunction "2_2") (pintype "passive"))
      (node (ref "R35") (pin "2") (pinfunction "2_2") (pintype "passive"))
    )
    (net (code "7") (name "BT_MIC_L") (class "Default")
      (node (ref "BC127") (pin "20") (pinfunction "MIC_LN_20") (pintype "input"))
      (node (ref "C35") (pin "1") (pinfunction "1_1") (pintype "passive"))
      (node (ref "MIC_IN") (pin "TIP") (pinfunction "LEFT_TIP") (pintype "bidirectional"))
      (node (ref "R24") (pin "1") (pinfunction "1_1") (pintype "passive"))
    )
    (net (code "8") (name "BT_URX") (class "Default")
      (node (ref "PIC24FJ1024GA606") (pin "5") (pinfunction "C1INC/RP26/OCM1B/PMA4/RG7_5") (pintype "bidirectional"))
      (node (ref "R26") (pin "2") (pinfunction "2_2") (pintype "passive"))
      (node (ref "TMUX154E") (pin "2") (pinfunction "A0_2") (pintype "bidirectional"))
    )
    (net (code "9") (name "BT_UTX") (class "Default")
      (node (ref "BC127") (pin "41") (pinfunction "UART_TX_41") (pintype "output"))
      (node (ref "PIC24FJ1024GA606") (pin "4") (pinfunction "C1IND/RP21/ICM1/OCM1A/PMA5/RG6_4") (pintype "bidirectional"))
      (node (ref "R27") (pin "1") (pinfunction "1_1") (pintype "passive"))
      (node (ref "TMUX154E") (pin "8") (pinfunction "B0_8") (pintype "bidirectional"))
    )
    (net (code "10") (name "CHG_EXT") (class "Default")
      (node (ref "BC127") (pin "29") (pinfunction "CHG_EXT_29") (pintype "power_in"))
    )
    (net (code "11") (name "DAC_OUT_L") (class "Default")
      (node (ref "FB3") (pin "1") (pinfunction "1_1") (pintype "bidirectional"))
      (node (ref "PCM5122") (pin "6") (pinfunction "OUTL_6") (pintype "output"))
      (node (ref "R39") (pin "1") (pinfunction "1_1") (pintype "passive"))
    )
    (net (code "12") (name "EE_CS") (class "Default")
      (node (ref "AT25M01") (pin "1") (pinfunction "CE_1") (pintype "bidirectional"))
      (node (ref "PIC24FJ1024GA606") (pin "42") (pinfunction "CLC4OUT/RP2/U6RTS/U6BCLK/ICM5/RD8_42") (pintype "bidirectional"))
      (node (ref "R11") (pin "1") (pinfunction "1_1") (pintype "passive"))
    )
    (net (code "13") (name "EE_SCK") (class "Default")
      (node (ref "AT25M01") (pin "6") (pinfunction "SCK_6") (pintype "bidirectional"))
      (node (ref "PIC24FJ1024GA606") (pin "33") (pinfunction "RP16/RF3_33") (pintype "bidirectional"))
    )
    (net (code "14") (name "EE_SI") (class "Default")
      (node (ref "AT25M01") (pin "5") (pinfunction "SI_5") (pintype "bidirectional"))
      (node (ref "PIC24FJ1024GA606") (pin "34") (pinfunction "RP30/RF2_34") (pintype "bidirectional"))
    )
    (net (code "15") (name "EE_SO") (class "Default")
      (node (ref "AT25M01") (pin "2") (pinfunction "SO_2") (pintype "bidirectional"))
      (node (ref "PIC24FJ1024GA606") (pin "43") (pinfunction "RP4/PMACK2/RD9_43") (pintype "bidirectional"))
    )
    (net (code "16") (name "GND") (class "Default")
      (node (ref "AT25M01") (pin "4") (pinfunction "VSS_4") (pintype "power_in"))
      (node (ref "BC127") (pin "1") (pinfunction "GND_1") (pintype "bidirectional"))
      (node (ref "BC127") (pin "11") (pinfunction "GND_11") (pintype "bidirectional"))
      (node (ref "BC127") (pin "2") (pinfunction "GND_2") (pintype "bidirectional"))
      (node (ref "BC127") (pin "22") (pinfunction "GND_22") (pintype "bidirectional"))
      (node (ref "BC127") (pin "27") (pinfunction "GND_27") (pintype "bidirectional"))
      (node (ref "BC127") (pin "3") (pinfunction "GND_3") (pintype "bidirectional"))
      (node (ref "BC127") (pin "4") (pinfunction "GND_4") (pintype "bidirectional"))
      (node (ref "BC127") (pin "45") (pinfunction "SPI_PCM#_45") (pintype "input"))
      (node (ref "C1") (pin "2") (pinfunction "2_2") (pintype "passive"))
      (node (ref "C10") (pin "2") (pinfunction "2_2") (pintype "passive"))
      (node (ref "C12") (pin "2") (pinfunction "2_2") (pintype "passive"))
      (node (ref "C13") (pin "2") (pinfunction "2_2") (pintype "passive"))
      (node (ref "C14") (pin "2") (pinfunction "2_2") (pintype "passive"))
      (node (ref "C15") (pin "1") (pinfunction "1_1") (pintype "passive"))
      (node (ref "C16") (pin "1") (pinfunction "1_1") (pintype "passive"))
      (node (ref "C17") (pin "1") (pinfunction "1_1") (pintype "passive"))
      (node (ref "C18") (pin "2") (pinfunction "2_2") (pintype "passive"))
      (node (ref "C19") (pin "2") (pinfunction "2_2") (pintype "passive"))
      (node (ref "C2") (pin "2") (pinfunction "2_2") (pintype "passive"))
      (node (ref "C20") (pin "1") (pinfunction "1_1") (pintype "passive"))
      (node (ref "C21") (pin "1") (pinfunction "1_1") (pintype "passive"))
      (node (ref "C22") (pin "2") (pinfunction "2_2") (pintype "passive"))
      (node (ref "C23") (pin "2") (pinfunction "2_2") (pintype "passive"))
      (node (ref "C24") (pin "2") (pinfunction "2_2") (pintype "passive"))
      (node (ref "C25") (pin "2") (pinfunction "2_2") (pintype "passive"))
      (node (ref "C26") (pin "2") (pinfunction "2_2") (pintype "passive"))
      (node (ref "C27") (pin "2") (pinfunction "2_2") (pintype "passive"))
      (node (ref "C3") (pin "2") (pinfunction "2_2") (pintype "passive"))
      (node (ref "C30") (pin "2") (pinfunction "2_2") (pintype "passive"))
      (node (ref "C31") (pin "2") (pinfunction "2_2") (pintype "passive"))
      (node (ref "C32") (pin "2") (pinfunction "2_2") (pintype "passive"))
      (node (ref "C33") (pin "2") (pinfunction "2_2") (pintype "passive"))
      (node (ref "C36") (pin "2") (pinfunction "2_2") (pintype "passive"))
      (node (ref "C37") (pin "2") (pinfunction "2_2") (pintype "passive"))
      (node (ref "C38") (pin "2") (pinfunction "2_2") (pintype "passive"))
      (node (ref "C39") (pin "2") (pinfunction "2_2") (pintype "passive"))
      (node (ref "C4") (pin "2") (pinfunction "2_2") (pintype "passive"))
      (node (ref "C40") (pin "2") (pinfunction "2_2") (pintype "passive"))
      (node (ref "C41") (pin "2") (pinfunction "2_2") (pintype "passive"))
      (node (ref "C42") (pin "2") (pinfunction "2_2") (pintype "passive"))
      (node (ref "C44") (pin "2") (pinfunction "2_2") (pintype "passive"))
      (node (ref "C5") (pin "2") (pinfunction "2_2") (pintype "passive"))
      (node (ref "C53") (pin "2") (pinfunction "2_2") (pintype "passive"))
      (node (ref "C54") (pin "2") (pinfunction "2_2") (pintype "passive"))
      (node (ref "C55") (pin "2") (pinfunction "2_2") (pintype "passive"))
      (node (ref "C56") (pin "2") (pinfunction "2_2") (pintype "passive"))
      (node (ref "C6") (pin "2") (pinfunction "2_2") (pintype "passive"))
      (node (ref "C8") (pin "2") (pinfunction "2_2") (pintype "passive"))
      (node (ref "C9") (pin "2") (pinfunction "2_2") (pintype "passive"))
      (node (ref "DSP_OUT") (pin "1") (pinfunction "GND_1") (pintype "bidirectional"))
      (node (ref "DSP_OUT") (pin "2") (pinfunction "GND_2") (pintype "bidirectional"))
      (node (ref "DSP_OUT") (pin "3") (pinfunction "GND_3") (pintype "bidirectional"))
      (node (ref "DSP_OUT") (pin "4") (pinfunction "GND_4") (pintype "bidirectional"))
      (node (ref "FT231X") (pin "16") (pinfunction "GND_16") (pintype "bidirectional"))
      (node (ref "FT231X") (pin "6") (pinfunction "GND_6") (pintype "bidirectional"))
      (node (ref "H1") (pin "B2.2") (pinfunction "MOUNT_B2.2") (pintype "passive"))
      (node (ref "H2") (pin "B2.2") (pinfunction "MOUNT_B2.2") (pintype "passive"))
      (node (ref "H3") (pin "B2.2") (pinfunction "MOUNT_B2.2") (pintype "passive"))
      (node (ref "H4") (pin "B2.2") (pinfunction "MOUNT_B2.2") (pintype "passive"))
      (node (ref "L1") (pin "2") (pinfunction "2_2") (pintype "passive"))
      (node (ref "L1") (pin "3") (pinfunction "3_3") (pintype "passive"))
      (node (ref "MIC_IN") (pin "SLEEVE") (pinfunction "SLEEVE_SLEEVE") (pintype "bidirectional"))
      (node (ref "MPQ4420") (pin "4") (pinfunction "GND_4") (pintype "bidirectional"))
      (node (ref "PAM8406") (pin "10") (pinfunction "INR_10") (pintype "input"))
      (node (ref "PAM8406") (pin "11") (pinfunction "GND_11") (pintype "bidirectional"))
      (node (ref "PAM8406") (pin "15") (pinfunction "PGNDR_15") (pintype "bidirectional"))
      (node (ref "PAM8406") (pin "2") (pinfunction "PGNDL_2") (pintype "bidirectional"))
      (node (ref "PCM5122") (pin "16") (pinfunction "ADR2/GPIO2/DOUT_16") (pintype "bidirectional"))
      (node (ref "PCM5122") (pin "17") (pinfunction "MODE1_17") (pintype "bidirectional"))
      (node (ref "PCM5122") (pin "24") (pinfunction "ADR1/MISO/FMT_24") (pintype "input"))
      (node (ref "PCM5122") (pin "27") (pinfunction "DGND_27") (pintype "bidirectional"))
      (node (ref "PIC24FJ1024GA606") (pin "20") (pinfunction "AVSS_20") (pintype "power_in"))
      (node (ref "PIC24FJ1024GA606") (pin "25") (pinfunction "VSS_25") (pintype "power_in"))
      (node (ref "PIC24FJ1024GA606") (pin "41") (pinfunction "VSS_41") (pintype "power_in"))
      (node (ref "PIC24FJ1024GA606") (pin "9") (pinfunction "VSS_9") (pintype "power_in"))
      (node (ref "PICKIT") (pin "4") (pinfunction "4_4") (pintype "bidirectional"))
      (node (ref "PWR") (pin "-") (pinfunction "C_-") (pintype "passive"))
      (node (ref "PWR_IN") (pin "1") (pinfunction "1_1") (pintype "passive"))
      (node (ref "Q1") (pin "2") (pinfunction "S_2") (pintype "bidirectional"))
      (node (ref "Q3") (pin "2") (pinfunction "S_2") (pintype "bidirectional"))
      (node (ref "Q4") (pin "2") (pinfunction "S_2") (pintype "bidirectional"))
      (node (ref "R22") (pin "1") (pinfunction "1_1") (pintype "passive"))
      (node (ref "R28") (pin "1") (pinfunction "1_1") (pintype "passive"))
      (node (ref "R3") (pin "1") (pinfunction "1_1") (pintype "passive"))
      (node (ref "R32") (pin "1") (pinfunction "1_1") (pintype "passive"))
      (node (ref "R34") (pin "1") (pinfunction "1_1") (pintype "passive"))
      (node (ref "R35") (pin "1") (pinfunction "1_1") (pintype "passive"))
      (node (ref "R4") (pin "1") (pinfunction "1_1") (pintype "passive"))
      (node (ref "R9") (pin "1") (pinfunction "1_1") (pintype "passive"))
      (node (ref "RECOVERY") (pin "1") (pinfunction "1_1") (pintype "passive"))
      (node (ref "S1212BC0") (pin "2") (pinfunction "GND_2") (pintype "power_in"))
      (node (ref "SH1") (pin "1") (pinfunction "P$1_1") (pintype "bidirectional"))
      (node (ref "TCU_IO") (pin "4") (pinfunction "4_4") (pintype "bidirectional"))
      (node (ref "TH3122") (pin "12") (pinfunction "GND3_12") (pintype "passive"))
      (node (ref "TH3122") (pin "13") (pinfunction "GND4_13") (pintype "passive"))
      (node (ref "TH3122") (pin "3") (pinfunction "VTR_3") (pintype "input"))
      (node (ref "TH3122") (pin "4") (pinfunction "GND1_4") (pintype "passive"))
      (node (ref "TH3122") (pin "5") (pinfunction "GND2_5") (pintype "passive"))
      (node (ref "TH3122") (pin "7") (pinfunction "SI_7") (pintype "bidirectional"))
      (node (ref "TMUX154E") (pin "5") (pinfunction "GND_5") (pintype "power_in"))
      (node (ref "TMUX154E") (pin "9") (pinfunction "EN_9") (pintype "input"))
      (node (ref "USB") (pin "5") (pinfunction "GND_5") (pintype "power_in"))
      (node (ref "USB") (pin "MNT1") (pinfunction "SHIELD_MNT1") (pintype "bidirectional"))
      (node (ref "USB") (pin "MNT2") (pinfunction "SHIELD_MNT2") (pintype "bidirectional"))
      (node (ref "USB") (pin "MNT3") (pinfunction "SHIELD_MNT3") (pintype "bidirectional"))
      (node (ref "USB") (pin "MNT4") (pinfunction "SHIELD_MNT4") (pintype "bidirectional"))
      (node (ref "WM8804") (pin "18") (pinfunction "DGND_18") (pintype "power_in"))
      (node (ref "WM8804") (pin "8") (pinfunction "PGND_8") (pintype "power_in"))
      (node (ref "XC6210") (pin "2") (pinfunction "GND_2") (pintype "power_in"))
    )
    (net (code "17") (name "I2S_CLK") (class "Default")
      (node (ref "PCM5122") (pin "21") (pinfunction "BCK_21") (pintype "input"))
      (node (ref "WM8804") (pin "14") (pinfunction "BCLK_14") (pintype "bidirectional"))
    )
    (net (code "18") (name "I2S_DOUT") (class "Default")
      (node (ref "PCM5122") (pin "22") (pinfunction "DIN_22") (pintype "input"))
      (node (ref "WM8804") (pin "12") (pinfunction "DOUT_12") (pintype "output"))
    )
    (net (code "19") (name "I2S_LRCK") (class "Default")
      (node (ref "PCM5122") (pin "23") (pinfunction "LRCK_23") (pintype "input"))
      (node (ref "WM8804") (pin "15") (pinfunction "LRCLK_15") (pintype "bidirectional"))
    )
    (net (code "20") (name "I2S_SCK") (class "Default")
      (node (ref "PCM5122") (pin "20") (pinfunction "SCK_20") (pintype "input"))
      (node (ref "WM8804") (pin "16") (pinfunction "MCLK_16") (pintype "bidirectional"))
    )
    (net (code "21") (name "IBUS") (class "Default")
      (node (ref "PWR_IN") (pin "3") (pinfunction "3_3") (pintype "passive"))
      (node (ref "R14") (pin "1") (pinfunction "1_1") (pintype "passive"))
    )
    (net (code "22") (name "IBUS_5V") (class "Default")
      (node (ref "C21") (pin "2") (pinfunction "2_2") (pintype "passive"))
      (node (ref "R6") (pin "2") (pinfunction "2_2") (pintype "passive"))
      (node (ref "TH3122") (pin "16") (pinfunction "VCC_16") (pintype "passive"))
    )
    (net (code "23") (name "IBUS_EN") (class "Default")
      (node (ref "PIC24FJ1024GA606") (pin "59") (pinfunction "RF1_59") (pintype "bidirectional"))
      (node (ref "TH3122") (pin "2") (pinfunction "EN_2") (pintype "input"))
    )
    (net (code "24") (name "IBUS_URX") (class "Default")
      (node (ref "PIC24FJ1024GA606") (pin "45") (pinfunction "RP12/PMA14/PMCS1/RD11_45") (pintype "bidirectional"))
      (node (ref "TH3122") (pin "10") (pinfunction "RXD_10") (pintype "output"))
    )
    (net (code "25") (name "IBUS_USTA") (class "Default")
      (node (ref "PIC24FJ1024GA606") (pin "46") (pinfunction "CLC3OUT/RP11/U6CTS/ICM6/RD0_46") (pintype "bidirectional"))
      (node (ref "TH3122") (pin "9") (pinfunction "SEN/STA_9") (pintype "bidirectional"))
    )
    (net (code "26") (name "IBUS_UTX") (class "Default")
      (node (ref "PIC24FJ1024GA606") (pin "44") (pinfunction "RP3/PMA15/PMCS2/RD10_44") (pintype "bidirectional"))
      (node (ref "TH3122") (pin "11") (pinfunction "TXD_11") (pintype "input"))
    )
    (net (code "27") (name "MCU_MCLR") (class "Default")
      (node (ref "PIC24FJ1024GA606") (pin "7") (pinfunction "MCLR_7") (pintype "bidirectional"))
      (node (ref "PICKIT") (pin "6") (pinfunction "6_6") (pintype "bidirectional"))
      (node (ref "R12") (pin "2") (pinfunction "2_2") (pintype "passive"))
    )
    (net (code "28") (name "MCU_PGC") (class "Default")
      (node (ref "PIC24FJ1024GA606") (pin "15") (pinfunction "PGEC1_15") (pintype "bidirectional"))
      (node (ref "PICKIT") (pin "5") (pinfunction "5_5") (pintype "bidirectional"))
    )
    (net (code "29") (name "MCU_PGD") (class "Default")
      (node (ref "PIC24FJ1024GA606") (pin "16") (pinfunction "PGED1_16") (pintype "bidirectional"))
      (node (ref "PICKIT") (pin "3") (pinfunction "3_3") (pintype "bidirectional"))
    )
    (net (code "30") (name "MCU_RECOV") (class "Default")
      (node (ref "PIC24FJ1024GA606") (pin "53") (pinfunction "RP20/PMRD/PMWR/RD5_53") (pintype "bidirectional"))
      (node (ref "R15") (pin "1") (pinfunction "1_1") (pintype "passive"))
      (node (ref "RECOVERY") (pin "2") (pinfunction "2_2") (pintype "passive"))
    )
    (net (code "31") (name "MCU_SCK3") (class "Default")
      (node (ref "PCM5122") (pin "12") (pinfunction "SCL/MC/ATT1_12") (pintype "bidirectional"))
      (node (ref "PIC24FJ1024GA606") (pin "2") (pinfunction "SCL3/IC5/PMD6/RE6_2") (pintype "bidirectional"))
      (node (ref "R33") (pin "2") (pinfunction "2_2") (pintype "passive"))
      (node (ref "WM8804") (pin "1") (pinfunction "SCLK_1") (pintype "input"))
    )
    (net (code "32") (name "MCU_SDA3") (class "Default")
      (node (ref "PCM5122") (pin "11") (pinfunction "SDA/MOSI/ATT2_11") (pintype "bidirectional"))
      (node (ref "PIC24FJ1024GA606") (pin "3") (pinfunction "SDA3/IC6/PMD7/RE7_3") (pintype "bidirectional"))
      (node (ref "R31") (pin "2") (pinfunction "2_2") (pintype "passive"))
      (node (ref "WM8804") (pin "3") (pinfunction "SDIN/HWMODE_3") (pintype "input"))
    )
    (net (code "33") (name "MCU_TEL_MUTE") (class "Default")
      (node (ref "PIC24FJ1024GA606") (pin "62") (pinfunction "PMD2/RE2_62") (pintype "bidirectional"))
      (node (ref "Q1") (pin "1") (pinfunction "G_1") (pintype "bidirectional"))
      (node (ref "R4") (pin "2") (pinfunction "2_2") (pintype "passive"))
    )
    (net (code "34") (name "MCU_TEL_ON") (class "Default")
      (node (ref "PIC24FJ1024GA606") (pin "18") (pinfunction "PGED2/AN7/RP7/U6TX/RB7_18") (pintype "bidirectional"))
      (node (ref "Q3") (pin "1") (pinfunction "G_1") (pintype "bidirectional"))
      (node (ref "R3") (pin "2") (pinfunction "2_2") (pintype "passive"))
    )
    (net (code "35") (name "MCU_URX") (class "Default")
      (node (ref "PIC24FJ1024GA606") (pin "50") (pinfunction "RP23/PMACK1/RD2_50") (pintype "bidirectional"))
      (node (ref "R16") (pin "1") (pinfunction "1_1") (pintype "passive"))
      (node (ref "TMUX154E") (pin "3") (pinfunction "A1_3") (pintype "bidirectional"))
    )
    (net (code "36") (name "MCU_UTX") (class "Default")
      (node (ref "PIC24FJ1024GA606") (pin "49") (pinfunction "RP24/U5TX/ICM4/RD1_49") (pintype "bidirectional"))
      (node (ref "R18") (pin "1") (pinfunction "1_1") (pintype "passive"))
      (node (ref "TMUX154E") (pin "7") (pinfunction "B1_7") (pintype "bidirectional"))
    )
    (net (code "37") (name "Net-(BC127-MIC_BIAS)") (class "Default")
      (node (ref "BC127") (pin "17") (pinfunction "MIC_BIAS_17") (pintype "input"))
      (node (ref "BC127") (pin "21") (pinfunction "MIC_LP_21") (pintype "input"))
      (node (ref "R24") (pin "2") (pinfunction "2_2") (pintype "passive"))
    )
    (net (code "38") (name "Net-(BC127-RST#)") (class "Default")
      (node (ref "BC127") (pin "44") (pinfunction "RST#_44") (pintype "input"))
      (node (ref "R25") (pin "1") (pinfunction "1_1") (pintype "passive"))
    )
    (net (code "39") (name "Net-(BC127-UART_RX)") (class "Default")
      (node (ref "BC127") (pin "42") (pinfunction "UART_RX_42") (pintype "input"))
      (node (ref "R26") (pin "1") (pinfunction "1_1") (pintype "passive"))
    )
    (net (code "40") (name "Net-(BC127-VREGEN)") (class "Default")
      (node (ref "BC127") (pin "28") (pinfunction "VREGEN_28") (pintype "output"))
      (node (ref "Q4") (pin "3") (pinfunction "D_3") (pintype "bidirectional"))
      (node (ref "R23") (pin "2") (pinfunction "2_2") (pintype "passive"))
    )
    (net (code "41") (name "Net-(C7-Pad1)") (class "Default")
      (node (ref "C7") (pin "1") (pinfunction "1_1") (pintype "passive"))
      (node (ref "R7") (pin "2") (pinfunction "2_2") (pintype "passive"))
    )
    (net (code "42") (name "Net-(C18-Pad1)") (class "Default")
      (node (ref "C18") (pin "1") (pinfunction "1_1") (pintype "passive"))
      (node (ref "R12") (pin "1") (pinfunction "1_1") (pintype "passive"))
      (node (ref "R13") (pin "2") (pinfunction "2_2") (pintype "passive"))
    )
    (net (code "43") (name "Net-(C29-Pad2)") (class "Default")
      (node (ref "C29") (pin "2") (pinfunction "2_2") (pintype "passive"))
      (node (ref "R28") (pin "2") (pinfunction "2_2") (pintype "passive"))
      (node (ref "R29") (pin "1") (pinfunction "1_1") (pintype "passive"))
    )
    (net (code "44") (name "Net-(C43-Pad1)") (class "Default")
      (node (ref "C43") (pin "1") (pinfunction "1_1") (pintype "passive"))
      (node (ref "FB3") (pin "2") (pinfunction "2_2") (pintype "bidirectional"))
    )
    (net (code "45") (name "Net-(C43-Pad2)") (class "Default")
      (node (ref "C43") (pin "2") (pinfunction "2_2") (pintype "passive"))
      (node (ref "R37") (pin "1") (pinfunction "1_1") (pintype "passive"))
    )
    (net (code "46") (name "Net-(F1-IN)") (class "Default")
      (node (ref "F1") (pin "OUT") (pinfunction "IN_OUT") (pintype "bidirectional"))
      (node (ref "L1") (pin "1") (pinfunction "1_1") (pintype "passive"))
    )
    (net (code "47") (name "Net-(F1-OUT)") (class "Default")
      (node (ref "D1") (pin "C") (pinfunction "C_C") (pintype "passive"))
      (node (ref "F1") (pin "IN") (pinfunction "OUT_IN") (pintype "bidirectional"))
    )
    (net (code "48") (name "Net-(FT231X-3V3OUT)") (class "Default")
      (node (ref "C27") (pin "1") (pinfunction "1_1") (pintype "passive"))
      (node (ref "FT231X") (pin "13") (pinfunction "3V3OUT_13") (pintype "bidirectional"))
      (node (ref "FT231X") (pin "14") (pinfunction "~{RESET}_14") (pintype "bidirectional"))
      (node (ref "FT231X") (pin "3") (pinfunction "VCCIO_3") (pintype "bidirectional"))
    )
    (net (code "49") (name "Net-(FT231X-CBUS1)") (class "Default")
      (node (ref "FT231X") (pin "17") (pinfunction "CBUS1_17") (pintype "bidirectional"))
      (node (ref "R20") (pin "2") (pinfunction "2_2") (pintype "passive"))
    )
    (net (code "50") (name "Net-(FT231X-CBUS2)") (class "Default")
      (node (ref "FT231X") (pin "10") (pinfunction "CBUS2_10") (pintype "bidirectional"))
      (node (ref "R21") (pin "2") (pinfunction "2_2") (pintype "passive"))
    )
    (net (code "51") (name "Net-(MPQ4420-BS)") (class "Default")
      (node (ref "MPQ4420") (pin "5") (pinfunction "BS_5") (pintype "bidirectional"))
      (node (ref "R7") (pin "1") (pinfunction "1_1") (pintype "passive"))
    )
    (net (code "52") (name "Net-(MPQ4420-EN)") (class "Default")
      (node (ref "MPQ4420") (pin "6") (pinfunction "EN_6") (pintype "bidirectional"))
      (node (ref "R6") (pin "1") (pinfunction "1_1") (pintype "passive"))
    )
    (net (code "53") (name "Net-(MPQ4420-FB)") (class "Default")
      (node (ref "MPQ4420") (pin "8") (pinfunction "FB_8") (pintype "bidirectional"))
      (node (ref "R8") (pin "2") (pinfunction "2_2") (pintype "passive"))
    )
    (net (code "54") (name "Net-(MPQ4420-PG)") (class "Default")
      (node (ref "MPQ4420") (pin "1") (pinfunction "PG_1") (pintype "bidirectional"))
      (node (ref "R5") (pin "1") (pinfunction "1_1") (pintype "passive"))
    )
    (net (code "55") (name "Net-(MPQ4420-SW)") (class "Default")
      (node (ref "C7") (pin "2") (pinfunction "2_2") (pintype "passive"))
      (node (ref "L2") (pin "1") (pinfunction "1_1") (pintype "passive"))
      (node (ref "MPQ4420") (pin "3") (pinfunction "SW_3") (pintype "bidirectional"))
    )
    (net (code "56") (name "Net-(MPQ4420-VCC)") (class "Default")
      (node (ref "C6") (pin "1") (pinfunction "1_1") (pintype "passive"))
      (node (ref "MPQ4420") (pin "7") (pinfunction "VCC_7") (pintype "bidirectional"))
      (node (ref "R5") (pin "2") (pinfunction "2_2") (pintype "passive"))
    )
    (net (code "57") (name "Net-(PAM8406-INL)") (class "Default")
      (node (ref "PAM8406") (pin "7") (pinfunction "INL_7") (pintype "input"))
      (node (ref "R37") (pin "2") (pinfunction "2_2") (pintype "passive"))
    )
    (net (code "58") (name "Net-(PAM8406-OUT_L+)") (class "Default")
      (node (ref "FB1") (pin "1") (pinfunction "1_1") (pintype "bidirectional"))
      (node (ref "PAM8406") (pin "1") (pinfunction "OUT_L+_1") (pintype "output"))
    )
    (net (code "59") (name "Net-(PAM8406-OUT_L-)") (class "Default")
      (node (ref "FB2") (pin "1") (pinfunction "1_1") (pintype "bidirectional"))
      (node (ref "PAM8406") (pin "3") (pinfunction "OUT_L-_3") (pintype "output"))
    )
    (net (code "60") (name "Net-(PAM8406-VREF)") (class "Default")
      (node (ref "C44") (pin "1") (pinfunction "1_1") (pintype "passive"))
      (node (ref "PAM8406") (pin "8") (pinfunction "VREF_8") (pintype "output"))
    )
    (net (code "61") (name "Net-(PCM5122-CAPM)") (class "Default")
      (node (ref "C50") (pin "2") (pinfunction "2_2") (pintype "passive"))
      (node (ref "PCM5122") (pin "4") (pinfunction "CAPM_4") (pintype "output"))
    )
    (net (code "62") (name "Net-(PCM5122-CAPP)") (class "Default")
      (node (ref "C50") (pin "1") (pinfunction "1_1") (pintype "passive"))
      (node (ref "PCM5122") (pin "2") (pinfunction "CAPP_2") (pintype "output"))
    )
    (net (code "63") (name "Net-(PCM5122-LDOO)") (class "Default")
      (node (ref "C55") (pin "1") (pinfunction "1_1") (pintype "passive"))
      (node (ref "C56") (pin "1") (pinfunction "1_1") (pintype "passive"))
      (node (ref "PCM5122") (pin "26") (pinfunction "LDOO_26") (pintype "power_in"))
    )
    (net (code "64") (name "Net-(PCM5122-OUTR)") (class "Default")
      (node (ref "PCM5122") (pin "7") (pinfunction "OUTR_7") (pintype "output"))
      (node (ref "R38") (pin "1") (pinfunction "1_1") (pintype "passive"))
    )
    (net (code "65") (name "Net-(PCM5122-VNEG)") (class "Default")
      (node (ref "C49") (pin "2") (pinfunction "2_2") (pintype "passive"))
      (node (ref "PCM5122") (pin "5") (pinfunction "VNEG_5") (pintype "output"))
    )
    (net (code "66") (name "Net-(PIC24FJ1024GA606-PMD0{slash}RE0)") (class "Default")
      (node (ref "PIC24FJ1024GA606") (pin "60") (pinfunction "PMD0/RE0_60") (pintype "bidirectional"))
      (node (ref "R19") (pin "2") (pinfunction "2_2") (pintype "passive"))
    )
    (net (code "67") (name "Net-(PIC24FJ1024GA606-VCAP)") (class "Default")
      (node (ref "C19") (pin "1") (pinfunction "1_1") (pintype "passive"))
      (node (ref "PIC24FJ1024GA606") (pin "56") (pinfunction "VCAP_56") (pintype "passive"))
    )
    (net (code "68") (name "Net-(PWR-A)") (class "Default")
      (node (ref "PWR") (pin "+") (pinfunction "A_+") (pintype "passive"))
      (node (ref "R19") (pin "1") (pinfunction "1_1") (pintype "passive"))
    )
    (net (code "69") (name "Net-(Q2-D)") (class "Default")
      (node (ref "Q2") (pin "3") (pinfunction "D_3") (pintype "bidirectional"))
      (node (ref "R1") (pin "1") (pinfunction "1_1") (pintype "passive"))
    )
    (net (code "70") (name "Net-(Q2-G)") (class "Default")
      (node (ref "Q2") (pin "1") (pinfunction "G_1") (pintype "bidirectional"))
      (node (ref "Q3") (pin "3") (pinfunction "D_3") (pintype "bidirectional"))
      (node (ref "R2") (pin "1") (pinfunction "1_1") (pintype "passive"))
    )
    (net (code "71") (name "Net-(Q4-G)") (class "Default")
      (node (ref "C28") (pin "2") (pinfunction "2_2") (pintype "passive"))
      (node (ref "Q4") (pin "1") (pinfunction "G_1") (pintype "bidirectional"))
      (node (ref "R22") (pin "2") (pinfunction "2_2") (pintype "passive"))
    )
    (net (code "72") (name "Net-(R10-Pad1)") (class "Default")
      (node (ref "R10") (pin "1") (pinfunction "1_1") (pintype "passive"))
      (node (ref "R8") (pin "1") (pinfunction "1_1") (pintype "passive"))
      (node (ref "R9") (pin "2") (pinfunction "2_2") (pintype "passive"))
    )
    (net (code "73") (name "Net-(RX-C)") (class "Default")
      (node (ref "R20") (pin "1") (pinfunction "1_1") (pintype "passive"))
      (node (ref "RX") (pin "-") (pinfunction "C_-") (pintype "passive"))
    )
    (net (code "74") (name "Net-(TH3122-IBUS)") (class "Default")
      (node (ref "C22") (pin "1") (pinfunction "1_1") (pintype "passive"))
      (node (ref "R14") (pin "2") (pinfunction "2_2") (pintype "passive"))
      (node (ref "TH3122") (pin "6") (pinfunction "IBUS_6") (pintype "bidirectional"))
    )
    (net (code "75") (name "Net-(TX-C)") (class "Default")
      (node (ref "R21") (pin "1") (pinfunction "1_1") (pintype "passive"))
      (node (ref "TX") (pin "-") (pinfunction "C_-") (pintype "passive"))
    )
    (net (code "76") (name "Net-(WM8804-CSB{slash}GPO1)") (class "Default")
      (node (ref "R34") (pin "2") (pinfunction "2_2") (pintype "passive"))
      (node (ref "WM8804") (pin "5") (pinfunction "CSB/GPO1_5") (pintype "input"))
    )
    (net (code "77") (name "Net-(WM8804-GPO0{slash}SWIFMODE)") (class "Default")
      (node (ref "R32") (pin "2") (pinfunction "2_2") (pintype "passive"))
      (node (ref "WM8804") (pin "2") (pinfunction "GPO0/SWIFMODE_2") (pintype "output"))
    )
    (net (code "78") (name "Net-(WM8804-RESETB)") (class "Default")
      (node (ref "R30") (pin "2") (pinfunction "2_2") (pintype "passive"))
      (node (ref "WM8804") (pin "6") (pinfunction "RESETB_6") (pintype "input"))
    )
    (net (code "79") (name "Net-(WM8804-RXO)") (class "Default")
      (node (ref "C34") (pin "1") (pinfunction "1_1") (pintype "passive"))
      (node (ref "WM8804") (pin "20") (pinfunction "RXO_20") (pintype "input"))
    )
    (net (code "80") (name "Net-(WM8804-TXO)") (class "Default")
      (node (ref "R29") (pin "2") (pinfunction "2_2") (pintype "passive"))
      (node (ref "WM8804") (pin "17") (pinfunction "TXO_17") (pintype "output"))
    )
    (net (code "81") (name "Net-(WM8804-XIN)") (class "Default")
      (node (ref "C31") (pin "1") (pinfunction "1_1") (pintype "passive"))
      (node (ref "WM8804") (pin "11") (pinfunction "XIN_11") (pintype "bidirectional"))
      (node (ref "X1") (pin "2") (pinfunction "2_2") (pintype "passive"))
    )
    (net (code "82") (name "Net-(WM8804-XOP)") (class "Default")
      (node (ref "C32") (pin "1") (pinfunction "1_1") (pintype "passive"))
      (node (ref "WM8804") (pin "10") (pinfunction "XOP_10") (pintype "bidirectional"))
      (node (ref "X1") (pin "1") (pinfunction "1_1") (pintype "passive"))
    )
    (net (code "83") (name "SPDIF_OUT") (class "Default")
      (node (ref "C29") (pin "1") (pinfunction "1_1") (pintype "passive"))
      (node (ref "DSP_OUT") (pin "P$1") (pinfunction "1_P$1") (pintype "passive"))
    )
    (net (code "84") (name "SPKR_OUT_L") (class "Default")
      (node (ref "C46") (pin "1") (pinfunction "1_1") (pintype "passive"))
      (node (ref "R39") (pin "2") (pinfunction "2_2") (pintype "passive"))
      (node (ref "SPKR_OUT") (pin "1") (pinfunction "1_1") (pintype "bidirectional"))
    )
    (net (code "85") (name "SPKR_OUT_R") (class "Default")
      (node (ref "C45") (pin "1") (pinfunction "1_1") (pintype "passive"))
      (node (ref "R38") (pin "2") (pinfunction "2_2") (pintype "passive"))
      (node (ref "SPKR_OUT") (pin "4") (pinfunction "4_4") (pintype "bidirectional"))
    )
    (net (code "86") (name "SYS_DTR") (class "Default")
      (node (ref "FT231X") (pin "1") (pinfunction "~{DTR}_1") (pintype "bidirectional"))
      (node (ref "PIC24FJ1024GA606") (pin "52") (pinfunction "RP25/PMWR/PMENB/RD4_52") (pintype "bidirectional"))
    )
    (net (code "87") (name "SYS_UART_SEL") (class "Default")
      (node (ref "PIC24FJ1024GA606") (pin "51") (pinfunction "RP22/ICM7/PMBE0/RD3_51") (pintype "bidirectional"))
      (node (ref "R17") (pin "2") (pinfunction "2_2") (pintype "passive"))
      (node (ref "TMUX154E") (pin "1") (pinfunction "SEL_1") (pintype "bidirectional"))
    )
    (net (code "88") (name "SYS_URX") (class "Default")
      (node (ref "FT231X") (pin "4") (pinfunction "RXD_4") (pintype "bidirectional"))
      (node (ref "TMUX154E") (pin "6") (pinfunction "B_6") (pintype "bidirectional"))
    )
    (net (code "89") (name "SYS_USB_DN") (class "Default")
      (node (ref "FT231X") (pin "12") (pinfunction "USBDM_12") (pintype "bidirectional"))
      (node (ref "USB") (pin "2") (pinfunction "D-_2") (pintype "bidirectional"))
    )
    (net (code "90") (name "SYS_USB_DP") (class "Default")
      (node (ref "FT231X") (pin "11") (pinfunction "USBDP_11") (pintype "bidirectional"))
      (node (ref "USB") (pin "3") (pinfunction "D+_3") (pintype "bidirectional"))
    )
    (net (code "91") (name "SYS_UTX") (class "Default")
      (node (ref "FT231X") (pin "20") (pinfunction "TXD_20") (pintype "bidirectional"))
      (node (ref "TMUX154E") (pin "4") (pinfunction "A_4") (pintype "bidirectional"))
    )
    (net (code "92") (name "TEL_AMP_SHDN") (class "Default")
      (node (ref "PAM8406") (pin "12") (pinfunction "SHDN_12") (pintype "input"))
      (node (ref "PIC24FJ1024GA606") (pin "63") (pinfunction "CTED9/PMD3/RE3_63") (pintype "bidirectional"))
    )
    (net (code "93") (name "TEL_MIC_L_OUT") (class "Default")
      (node (ref "C35") (pin "2") (pinfunction "2_2") (pintype "passive"))
      (node (ref "R36") (pin "2") (pinfunction "2_2") (pintype "passive"))
      (node (ref "TCU_IO") (pin "3") (pinfunction "3_3") (pintype "bidirectional"))
    )
    (net (code "94") (name "TEL_MUTE_IO") (class "Default")
      (node (ref "Q1") (pin "3") (pinfunction "D_3") (pintype "bidirectional"))
      (node (ref "TCU_IO") (pin "6") (pinfunction "6_6") (pintype "bidirectional"))
    )
    (net (code "95") (name "TEL_ON_IO") (class "Default")
      (node (ref "R1") (pin "2") (pinfunction "2_2") (pintype "passive"))
      (node (ref "TCU_IO") (pin "5") (pinfunction "5_5") (pintype "bidirectional"))
    )
    (net (code "96") (name "TEL_OUT_L+") (class "Default")
      (node (ref "C39") (pin "1") (pinfunction "1_1") (pintype "passive"))
      (node (ref "FB1") (pin "2") (pinfunction "2_2") (pintype "bidirectional"))
      (node (ref "TCU_IO") (pin "1") (pinfunction "1_1") (pintype "bidirectional"))
    )
    (net (code "97") (name "TEL_OUT_L-") (class "Default")
      (node (ref "C40") (pin "1") (pinfunction "1_1") (pintype "passive"))
      (node (ref "FB2") (pin "2") (pinfunction "2_2") (pintype "bidirectional"))
      (node (ref "TCU_IO") (pin "2") (pinfunction "2_2") (pintype "bidirectional"))
    )
    (net (code "98") (name "USB_5V") (class "Default")
      (node (ref "D2") (pin "A") (pinfunction "A_A") (pintype "passive"))
      (node (ref "USB") (pin "1") (pinfunction "VBUS_1") (pintype "power_in"))
    )
    (net (code "99") (name "VBAT") (class "Default")
      (node (ref "D1") (pin "A") (pinfunction "A_A") (pintype "passive"))
      (node (ref "PWR_IN") (pin "2") (pinfunction "2_2") (pintype "passive"))
    )
    (net (code "100") (name "VBAT_SENSE") (class "Default")
      (node (ref "BC127") (pin "31") (pinfunction "VBAT_SENSE_31") (pintype "power_in"))
    )
    (net (code "101") (name "VCHG") (class "Default")
      (node (ref "BC127") (pin "30") (pinfunction "VCHG_30") (pintype "power_in"))
    )
    (net (code "102") (name "VIN") (class "Default")
      (node (ref "C1") (pin "1") (pinfunction "1_1") (pintype "passive"))
      (node (ref "C10") (pin "1") (pinfunction "1_1") (pintype "passive"))
      (node (ref "C23") (pin "1") (pinfunction "1_1") (pintype "passive"))
      (node (ref "C5") (pin "1") (pinfunction "1_1") (pintype "passive"))
      (node (ref "C8") (pin "1") (pinfunction "1_1") (pintype "passive"))
      (node (ref "C9") (pin "1") (pinfunction "1_1") (pintype "passive"))
      (node (ref "L1") (pin "4") (pinfunction "4_4") (pintype "passive"))
      (node (ref "MPQ4420") (pin "2") (pinfunction "IN_2") (pintype "bidirectional"))
      (node (ref "S1212BC0") (pin "1") (pinfunction "VIN_1") (pintype "power_in"))
      (node (ref "TH3122") (pin "1") (pinfunction "VS_1") (pintype "power_in"))
    )
    (net (code "103") (name "unconnected-(BC127-AIO-Pad12)") (class "Default")
      (node (ref "BC127") (pin "12") (pinfunction "AIO_12") (pintype "bidirectional"))
    )
    (net (code "104") (name "unconnected-(BC127-CAP_SENSE_1-Pad7)") (class "Default")
      (node (ref "BC127") (pin "7") (pinfunction "CAP_SENSE_1_7") (pintype "input"))
    )
    (net (code "105") (name "unconnected-(BC127-CAP_SENSE_2-Pad8)") (class "Default")
      (node (ref "BC127") (pin "8") (pinfunction "CAP_SENSE_2_8") (pintype "input"))
    )
    (net (code "106") (name "unconnected-(BC127-CAP_SENSE_3-Pad9)") (class "Default")
      (node (ref "BC127") (pin "9") (pinfunction "CAP_SENSE_3_9") (pintype "input"))
    )
    (net (code "107") (name "unconnected-(BC127-CAP_SENSE_4-Pad10)") (class "Default")
      (node (ref "BC127") (pin "10") (pinfunction "CAP_SENSE_4_10") (pintype "input"))
    )
    (net (code "108") (name "unconnected-(BC127-LED_0-Pad37)") (class "Default")
      (node (ref "BC127") (pin "37") (pinfunction "LED_0_37") (pintype "output"))
    )
    (net (code "109") (name "unconnected-(BC127-LED_1-Pad38)") (class "Default")
      (node (ref "BC127") (pin "38") (pinfunction "LED_1_38") (pintype "output"))
    )
    (net (code "110") (name "unconnected-(BC127-LED_2-Pad39)") (class "Default")
      (node (ref "BC127") (pin "39") (pinfunction "LED_2_39") (pintype "output"))
    )
    (net (code "111") (name "unconnected-(BC127-MIC_RN-Pad18)") (class "Default")
      (node (ref "BC127") (pin "18") (pinfunction "MIC_RN_18") (pintype "input"))
    )
    (net (code "112") (name "unconnected-(BC127-MIC_RP-Pad19)") (class "Default")
      (node (ref "BC127") (pin "19") (pinfunction "MIC_RP_19") (pintype "input"))
    )
    (net (code "113") (name "unconnected-(BC127-PCM1_CLK-Pad47)") (class "Default")
      (node (ref "BC127") (pin "47") (pinfunction "PCM1_CLK_47") (pintype "bidirectional"))
    )
    (net (code "114") (name "unconnected-(BC127-PCM1_IN-Pad49)") (class "Default")
      (node (ref "BC127") (pin "49") (pinfunction "PCM1_IN_49") (pintype "bidirectional"))
    )
    (net (code "115") (name "unconnected-(BC127-PCM1_SYNC-Pad46)") (class "Default")
      (node (ref "BC127") (pin "46") (pinfunction "PCM1_SYNC_46") (pintype "bidirectional"))
    )
    (net (code "116") (name "unconnected-(BC127-PIO_0-Pad23)") (class "Default")
      (node (ref "BC127") (pin "23") (pinfunction "PIO_0_23") (pintype "bidirectional"))
    )
    (net (code "117") (name "unconnected-(BC127-PIO_1-Pad24)") (class "Default")
      (node (ref "BC127") (pin "24") (pinfunction "PIO_1_24") (pintype "bidirectional"))
    )
    (net (code "118") (name "unconnected-(BC127-PIO_2-Pad50)") (class "Default")
      (node (ref "BC127") (pin "50") (pinfunction "PIO_2_50") (pintype "bidirectional"))
    )
    (net (code "119") (name "unconnected-(BC127-PIO_3-Pad51)") (class "Default")
      (node (ref "BC127") (pin "51") (pinfunction "PIO_3_51") (pintype "bidirectional"))
    )
    (net (code "120") (name "unconnected-(BC127-PIO_4{slash}PCM2_IN-Pad26)") (class "Default")
      (node (ref "BC127") (pin "26") (pinfunction "PIO_4/PCM2_IN_26") (pintype "bidirectional"))
    )
    (net (code "121") (name "unconnected-(BC127-PIO_6{slash}PCM2_SYNC-Pad5)") (class "Default")
      (node (ref "BC127") (pin "5") (pinfunction "PIO_6/PCM2_SYNC_5") (pintype "bidirectional"))
    )
    (net (code "122") (name "unconnected-(BC127-PIO_7{slash}PCM2_CLK-Pad6)") (class "Default")
      (node (ref "BC127") (pin "6") (pinfunction "PIO_7/PCM2_CLK_6") (pintype "bidirectional"))
    )
    (net (code "123") (name "unconnected-(BC127-SPKR_LN-Pad13)") (class "Default")
      (node (ref "BC127") (pin "13") (pinfunction "SPKR_LN_13") (pintype "output"))
    )
    (net (code "124") (name "unconnected-(BC127-SPKR_LP-Pad14)") (class "Default")
      (node (ref "BC127") (pin "14") (pinfunction "SPKR_LP_14") (pintype "output"))
    )
    (net (code "125") (name "unconnected-(BC127-SPKR_RN-Pad15)") (class "Default")
      (node (ref "BC127") (pin "15") (pinfunction "SPKR_RN_15") (pintype "output"))
    )
    (net (code "126") (name "unconnected-(BC127-SPKR_RP-Pad16)") (class "Default")
      (node (ref "BC127") (pin "16") (pinfunction "SPKR_RP_16") (pintype "output"))
    )
    (net (code "127") (name "unconnected-(BC127-UART_CTS-Pad40)") (class "Default")
      (node (ref "BC127") (pin "40") (pinfunction "UART_CTS_40") (pintype "input"))
    )
    (net (code "128") (name "unconnected-(BC127-UART_RTS-Pad43)") (class "Default")
      (node (ref "BC127") (pin "43") (pinfunction "UART_RTS_43") (pintype "output"))
    )
    (net (code "129") (name "unconnected-(BC127-USB_N-Pad35)") (class "Default")
      (node (ref "BC127") (pin "35") (pinfunction "USB_N_35") (pintype "bidirectional"))
    )
    (net (code "130") (name "unconnected-(BC127-USB_P-Pad36)") (class "Default")
      (node (ref "BC127") (pin "36") (pinfunction "USB_P_36") (pintype "bidirectional"))
    )
    (net (code "131") (name "unconnected-(FT231X-CBUS0-Pad18)") (class "Default")
      (node (ref "FT231X") (pin "18") (pinfunction "CBUS0_18") (pintype "bidirectional"))
    )
    (net (code "132") (name "unconnected-(FT231X-CBUS3-Pad19)") (class "Default")
      (node (ref "FT231X") (pin "19") (pinfunction "CBUS3_19") (pintype "bidirectional"))
    )
    (net (code "133") (name "unconnected-(FT231X-~{CTS}-Pad9)") (class "Default")
      (node (ref "FT231X") (pin "9") (pinfunction "~{CTS}_9") (pintype "bidirectional"))
    )
    (net (code "134") (name "unconnected-(FT231X-~{DCD}-Pad8)") (class "Default")
      (node (ref "FT231X") (pin "8") (pinfunction "~{DCD}_8") (pintype "bidirectional"))
    )
    (net (code "135") (name "unconnected-(FT231X-~{DSR}-Pad7)") (class "Default")
      (node (ref "FT231X") (pin "7") (pinfunction "~{DSR}_7") (pintype "bidirectional"))
    )
    (net (code "136") (name "unconnected-(FT231X-~{RI}-Pad5)") (class "Default")
      (node (ref "FT231X") (pin "5") (pinfunction "~{RI}_5") (pintype "bidirectional"))
    )
    (net (code "137") (name "unconnected-(FT231X-~{RTS}-Pad2)") (class "Default")
      (node (ref "FT231X") (pin "2") (pinfunction "~{RTS}_2") (pintype "bidirectional"))
    )
    (net (code "138") (name "unconnected-(MIC_IN-RIGHT-PadRING)") (class "Default")
      (node (ref "MIC_IN") (pin "RING") (pinfunction "RIGHT_RING") (pintype "bidirectional"))
    )
    (net (code "139") (name "unconnected-(PAM8406-MUTE-Pad5)") (class "Default")
      (node (ref "PAM8406") (pin "5") (pinfunction "MUTE_5") (pintype "input"))
    )
    (net (code "140") (name "unconnected-(PAM8406-OUT_R+-Pad16)") (class "Default")
      (node (ref "PAM8406") (pin "16") (pinfunction "OUT_R+_16") (pintype "output"))
    )
    (net (code "141") (name "unconnected-(PAM8406-OUT_R--Pad14)") (class "Default")
      (node (ref "PAM8406") (pin "14") (pinfunction "OUT_R-_14") (pintype "output"))
    )
    (net (code "142") (name "unconnected-(PCM5122-GPIO3{slash}AGNS-Pad15)") (class "Default")
      (node (ref "PCM5122") (pin "15") (pinfunction "GPIO3/AGNS_15") (pintype "bidirectional"))
    )
    (net (code "143") (name "unconnected-(PCM5122-GPIO4{slash}MAST-Pad14)") (class "Default")
      (node (ref "PCM5122") (pin "14") (pinfunction "GPIO4/MAST_14") (pintype "bidirectional"))
    )
    (net (code "144") (name "unconnected-(PCM5122-GPIO5{slash}ATT0-Pad13)") (class "Default")
      (node (ref "PCM5122") (pin "13") (pinfunction "GPIO5/ATT0_13") (pintype "bidirectional"))
    )
    (net (code "145") (name "unconnected-(PCM5122-GPIO6{slash}FLT-Pad19)") (class "Default")
      (node (ref "PCM5122") (pin "19") (pinfunction "GPIO6/FLT_19") (pintype "input"))
    )
    (net (code "146") (name "unconnected-(PIC24FJ1024GA606-AN2{slash}CTCMP{slash}C2INB{slash}RP13{slash}CTED13{slash}RB2-Pad14)") (class "Default")
      (node (ref "PIC24FJ1024GA606") (pin "14") (pinfunction "AN2/CTCMP/C2INB/RP13/CTED13/RB2_14") (pintype "bidirectional"))
    )
    (net (code "147") (name "unconnected-(PIC24FJ1024GA606-AN3{slash}C2INA{slash}RB3-Pad13)") (class "Default")
      (node (ref "PIC24FJ1024GA606") (pin "13") (pinfunction "AN3/C2INA/RB3_13") (pintype "bidirectional"))
    )
    (net (code "148") (name "unconnected-(PIC24FJ1024GA606-AN8{slash}RP8{slash}PWRGT{slash}RB8-Pad21)") (class "Default")
      (node (ref "PIC24FJ1024GA606") (pin "21") (pinfunction "AN8/RP8/PWRGT/RB8_21") (pintype "bidirectional"))
    )
    (net (code "149") (name "unconnected-(PIC24FJ1024GA606-AN9{slash}TMPR{slash}RP9{slash}T1CK{slash}PMA7{slash}RB9-Pad22)") (class "Default")
      (node (ref "PIC24FJ1024GA606") (pin "22") (pinfunction "AN9/TMPR/RP9/T1CK/PMA7/RB9_22") (pintype "bidirectional"))
    )
    (net (code "150") (name "unconnected-(PIC24FJ1024GA606-AN14{slash}RP14{slash}CTED5{slash}CTPLS{slash}PMA1{slash}PMALH{slash}RB14-Pad29)") (class "Default")
      (node (ref "PIC24FJ1024GA606") (pin "29") (pinfunction "AN14/RP14/CTED5/CTPLS/PMA1/PMALH/RB14_29") (pintype "bidirectional"))
    )
    (net (code "151") (name "unconnected-(PIC24FJ1024GA606-AN15{slash}RP29{slash}CTED6{slash}PMA0{slash}PMALL{slash}RB15-Pad30)") (class "Default")
      (node (ref "PIC24FJ1024GA606") (pin "30") (pinfunction "AN15/RP29/CTED6/PMA0/PMALL/RB15_30") (pintype "bidirectional"))
    )
    (net (code "152") (name "unconnected-(PIC24FJ1024GA606-C1INC{slash}C2INC{slash}C3INC{slash}RP27{slash}OCM2B{slash}PMA2{slash}PMALU{slash}RG9-Pad8)") (class "Default")
      (node (ref "PIC24FJ1024GA606") (pin "8") (pinfunction "C1INC/C2INC/C3INC/RP27/OCM2B/PMA2/PMALU/RG9_8") (pintype "bidirectional"))
    )
    (net (code "153") (name "unconnected-(PIC24FJ1024GA606-C2IND{slash}RP19{slash}ICM2{slash}OCM2A{slash}PMA3{slash}RG8-Pad6)") (class "Default")
      (node (ref "PIC24FJ1024GA606") (pin "6") (pinfunction "C2IND/RP19/ICM2/OCM2A/PMA3/RG8_6") (pintype "bidirectional"))
    )
    (net (code "154") (name "unconnected-(PIC24FJ1024GA606-C3INA{slash}U5RTS{slash}U5BCLK{slash}OC5{slash}RD7-Pad55)") (class "Default")
      (node (ref "PIC24FJ1024GA606") (pin "55") (pinfunction "C3INA/U5RTS/U5BCLK/OC5/RD7_55") (pintype "bidirectional"))
    )
    (net (code "155") (name "unconnected-(PIC24FJ1024GA606-C3INB{slash}U5RX{slash}OC4{slash}RD6-Pad54)") (class "Default")
      (node (ref "PIC24FJ1024GA606") (pin "54") (pinfunction "C3INB/U5RX/OC4/RD6_54") (pintype "bidirectional"))
    )
    (net (code "156") (name "unconnected-(PIC24FJ1024GA606-IC4{slash}CTED4{slash}PMD5{slash}RE5-Pad1)") (class "Default")
      (node (ref "PIC24FJ1024GA606") (pin "1") (pinfunction "IC4/CTED4/PMD5/RE5_1") (pintype "bidirectional"))
    )
    (net (code "157") (name "unconnected-(PIC24FJ1024GA606-INT0{slash}RF6-Pad35)") (class "Default")
      (node (ref "PIC24FJ1024GA606") (pin "35") (pinfunction "INT0/RF6_35") (pintype "bidirectional"))
    )
    (net (code "158") (name "unconnected-(PIC24FJ1024GA606-N{slash}C-Pad57)") (class "Default")
      (node (ref "PIC24FJ1024GA606") (pin "57") (pinfunction "N/C_57") (pintype "no_connect"))
    )
    (net (code "159") (name "unconnected-(PIC24FJ1024GA606-OSCI{slash}CLKI{slash}RC12-Pad39)") (class "Default")
      (node (ref "PIC24FJ1024GA606") (pin "39") (pinfunction "OSCI/CLKI/RC12_39") (pintype "bidirectional"))
    )
    (net (code "160") (name "unconnected-(PIC24FJ1024GA606-OSCO{slash}CLKO{slash}RC15-Pad40)") (class "Default")
      (node (ref "PIC24FJ1024GA606") (pin "40") (pinfunction "OSCO/CLKO/RC15_40") (pintype "bidirectional"))
    )
    (net (code "161") (name "unconnected-(PIC24FJ1024GA606-PGEC2{slash}AN6{slash}RP6{slash}RB6-Pad17)") (class "Default")
      (node (ref "PIC24FJ1024GA606") (pin "17") (pinfunction "PGEC2/AN6/RP6/RB6_17") (pintype "bidirectional"))
    )
    (net (code "162") (name "unconnected-(PIC24FJ1024GA606-PGEC3{slash}AN5{slash}C1INA{slash}RP18{slash}ICM3{slash}OCM3A{slash}RB5-Pad11)") (class "Default")
      (node (ref "PIC24FJ1024GA606") (pin "11") (pinfunction "PGEC3/AN5/C1INA/RP18/ICM3/OCM3A/RB5_11") (pintype "bidirectional"))
    )
    (net (code "163") (name "unconnected-(PIC24FJ1024GA606-PGED3{slash}AN4{slash}C1INB{slash}RP28{slash}OCM3B{slash}RB4-Pad12)") (class "Default")
      (node (ref "PIC24FJ1024GA606") (pin "12") (pinfunction "PGED3/AN4/C1INB/RP28/OCM3B/RB4_12") (pintype "bidirectional"))
    )
    (net (code "164") (name "unconnected-(PIC24FJ1024GA606-PMD1{slash}RE1-Pad61)") (class "Default")
      (node (ref "PIC24FJ1024GA606") (pin "61") (pinfunction "PMD1/RE1_61") (pintype "bidirectional"))
    )
    (net (code "165") (name "unconnected-(PIC24FJ1024GA606-RP10{slash}SDA2{slash}PMA9{slash}RF4-Pad31)") (class "Default")
      (node (ref "PIC24FJ1024GA606") (pin "31") (pinfunction "RP10/SDA2/PMA9/RF4_31") (pintype "bidirectional"))
    )
    (net (code "166") (name "unconnected-(PIC24FJ1024GA606-RP17{slash}SCL2{slash}PMA8{slash}RF5-Pad32)") (class "Default")
      (node (ref "PIC24FJ1024GA606") (pin "32") (pinfunction "RP17/SCL2/PMA8/RF5_32") (pintype "bidirectional"))
    )
    (net (code "167") (name "unconnected-(PIC24FJ1024GA606-SCL1{slash}RG2-Pad37)") (class "Default")
      (node (ref "PIC24FJ1024GA606") (pin "37") (pinfunction "SCL1/RG2_37") (pintype "bidirectional"))
    )
    (net (code "168") (name "unconnected-(PIC24FJ1024GA606-SDA1{slash}RG3-Pad36)") (class "Default")
      (node (ref "PIC24FJ1024GA606") (pin "36") (pinfunction "SDA1/RG3_36") (pintype "bidirectional"))
    )
    (net (code "169") (name "unconnected-(PIC24FJ1024GA606-SOSCI{slash}C3IND{slash}RC13-Pad47)") (class "Default")
      (node (ref "PIC24FJ1024GA606") (pin "47") (pinfunction "SOSCI/C3IND/RC13_47") (pintype "bidirectional"))
    )
    (net (code "170") (name "unconnected-(PIC24FJ1024GA606-SOSCO{slash}C3INC{slash}RPI37{slash}PWRLCLK{slash}RC14-Pad48)") (class "Default")
      (node (ref "PIC24FJ1024GA606") (pin "48") (pinfunction "SOSCO/C3INC/RPI37/PWRLCLK/RC14_48") (pintype "bidirectional"))
    )
    (net (code "171") (name "unconnected-(PIC24FJ1024GA606-TCK{slash}AN12{slash}U6RX{slash}CTED2{slash}PMA11{slash}RB12-Pad27)") (class "Default")
      (node (ref "PIC24FJ1024GA606") (pin "27") (pinfunction "TCK/AN12/U6RX/CTED2/PMA11/RB12_27") (pintype "bidirectional"))
    )
    (net (code "172") (name "unconnected-(PIC24FJ1024GA606-TDI{slash}AN13{slash}CTED1{slash}PMA10{slash}RB13-Pad28)") (class "Default")
      (node (ref "PIC24FJ1024GA606") (pin "28") (pinfunction "TDI/AN13/CTED1/PMA10/RB13_28") (pintype "bidirectional"))
    )
    (net (code "173") (name "unconnected-(PIC24FJ1024GA606-TDO{slash}AN11{slash}REFI{slash}PMA12{slash}RB11-Pad24)") (class "Default")
      (node (ref "PIC24FJ1024GA606") (pin "24") (pinfunction "TDO/AN11/REFI/PMA12/RB11_24") (pintype "bidirectional"))
    )
    (net (code "174") (name "unconnected-(PIC24FJ1024GA606-TMS{slash}CVREF{slash}AN10{slash}PMA13{slash}RB10-Pad23)") (class "Default")
      (node (ref "PIC24FJ1024GA606") (pin "23") (pinfunction "TMS/CVREF/AN10/PMA13/RB10_23") (pintype "bidirectional"))
    )
    (net (code "175") (name "unconnected-(PIC24FJ1024GA606-U5CTS{slash}OC6{slash}RF0-Pad58)") (class "Default")
      (node (ref "PIC24FJ1024GA606") (pin "58") (pinfunction "U5CTS/OC6/RF0_58") (pintype "bidirectional"))
    )
    (net (code "176") (name "unconnected-(S1212BC0-NC-Pad3)") (class "Default")
      (node (ref "S1212BC0") (pin "3") (pinfunction "NC_3") (pintype "no_connect"))
    )
    (net (code "177") (name "unconnected-(SPKR_OUT-Pad3)") (class "Default")
      (node (ref "SPKR_OUT") (pin "3") (pinfunction "3_3") (pintype "bidirectional"))
    )
    (net (code "178") (name "unconnected-(SPKR_OUT-Pad6)") (class "Default")
      (node (ref "SPKR_OUT") (pin "6") (pinfunction "6_6") (pintype "bidirectional"))
    )
    (net (code "179") (name "unconnected-(TH3122-RESET-Pad14)") (class "Default")
      (node (ref "TH3122") (pin "14") (pinfunction "RESET_14") (pintype "output"))
    )
    (net (code "180") (name "unconnected-(TH3122-SENSE-Pad15)") (class "Default")
      (node (ref "TH3122") (pin "15") (pinfunction "SENSE_15") (pintype "bidirectional"))
    )
    (net (code "181") (name "unconnected-(TH3122-SO-Pad8)") (class "Default")
      (node (ref "TH3122") (pin "8") (pinfunction "SO_8") (pintype "output"))
    )
    (net (code "182") (name "unconnected-(USB-ID-Pad4)") (class "Default")
      (node (ref "USB") (pin "4") (pinfunction "ID_4") (pintype "bidirectional"))
    )
    (net (code "183") (name "unconnected-(WM8804-CLKOUT-Pad9)") (class "Default")
      (node (ref "WM8804") (pin "9") (pinfunction "CLKOUT_9") (pintype "output"))
    )
    (net (code "184") (name "unconnected-(WM8804-DIN-Pad13)") (class "Default")
      (node (ref "WM8804") (pin "13") (pinfunction "DIN_13") (pintype "input"))
    )
    (net (code "185") (name "unconnected-(WM8804-SDOUT{slash}GPO2-Pad4)") (class "Default")
      (node (ref "WM8804") (pin "4") (pinfunction "SDOUT/GPO2_4") (pintype "output"))
    )
    (net (code "186") (name "unconnected-(XC6210-NC-Pad4)") (class "Default")
      (node (ref "XC6210") (pin "4") (pinfunction "NC_4") (pintype "no_connect"))
    )
  )
)
